# EEZ_DIB_MCU_r1B3.net
KiCad netlist of a schematic drawn in EAGLE
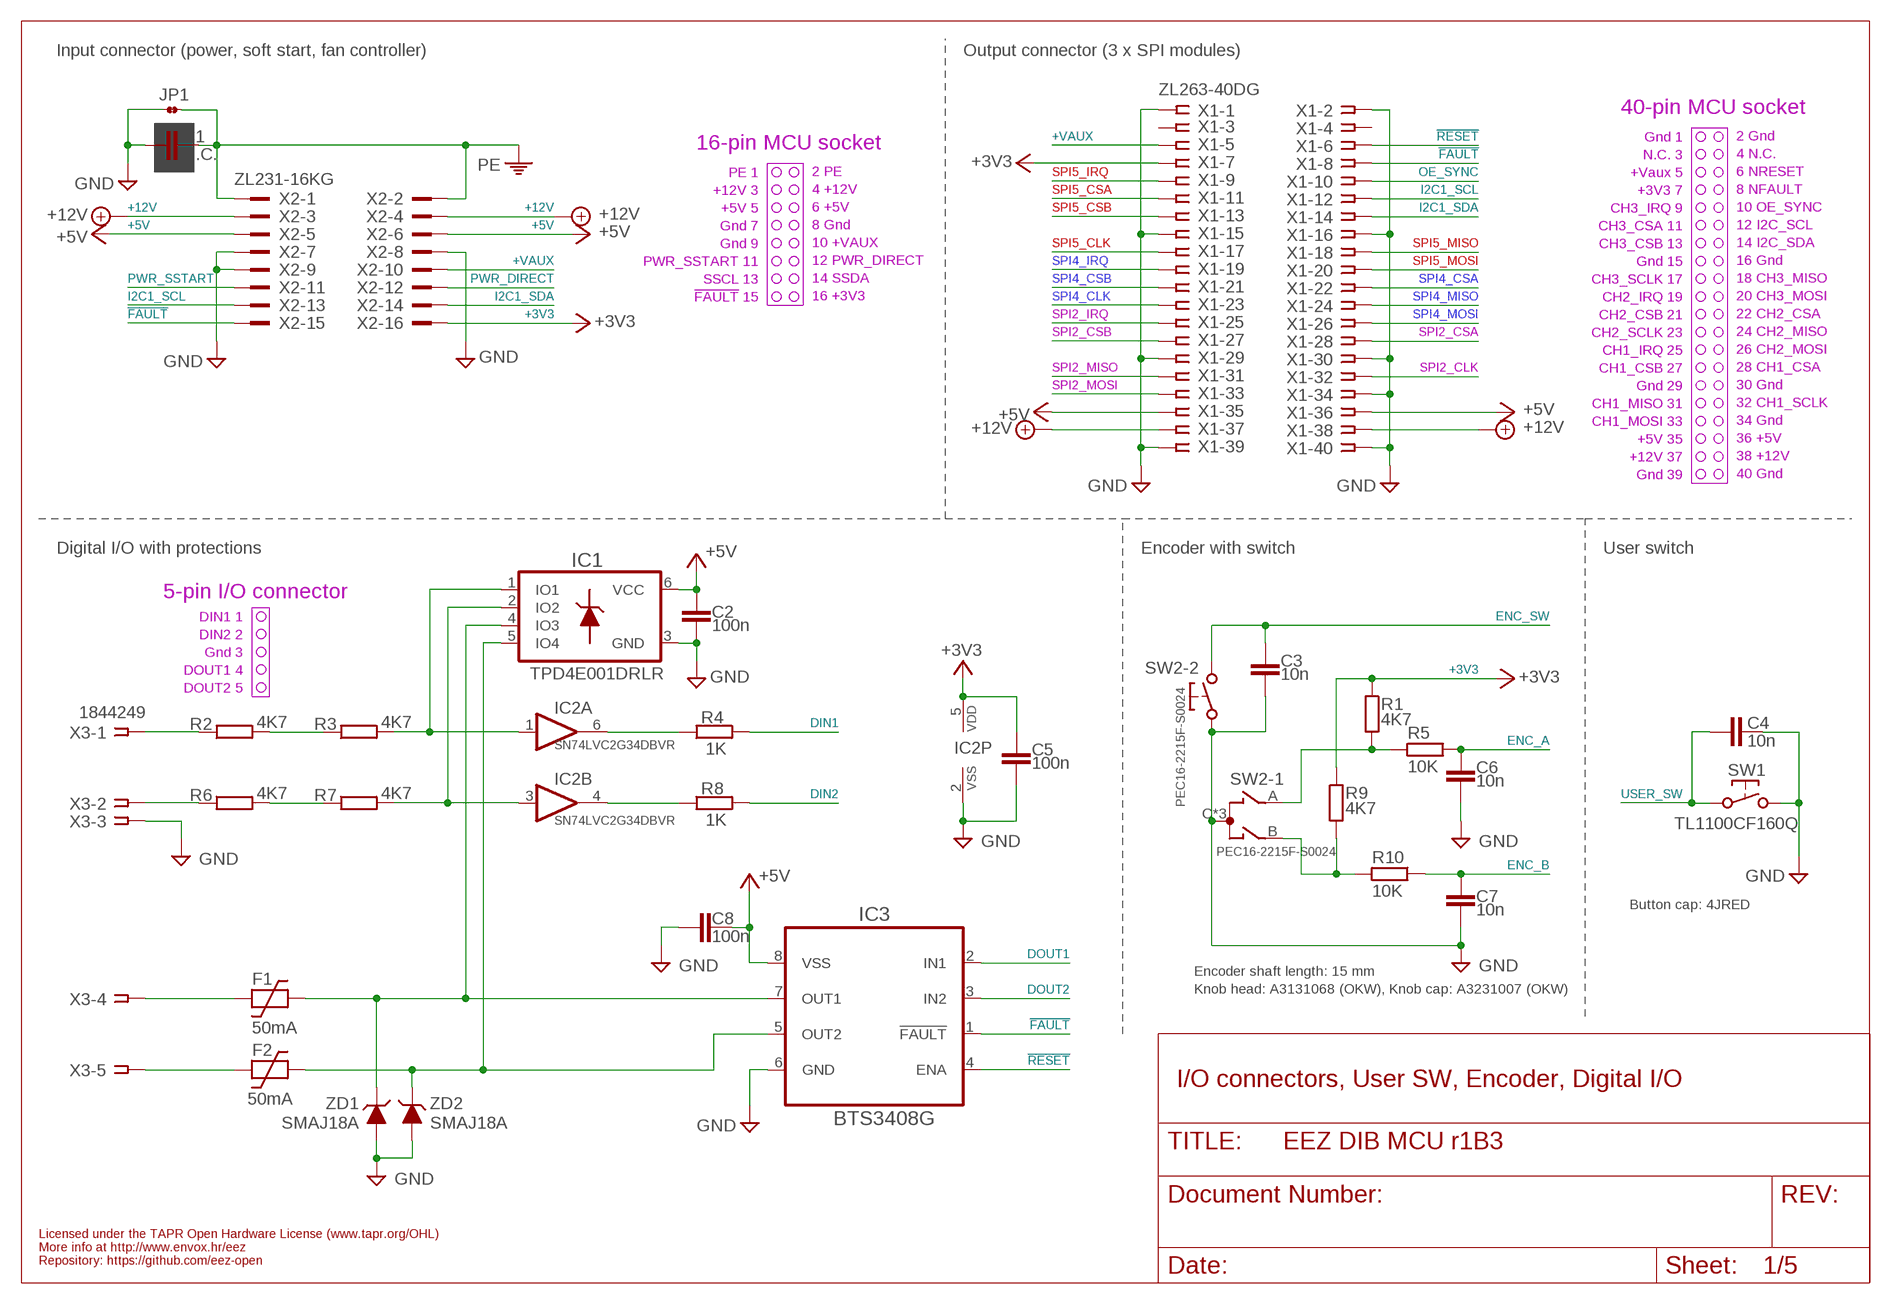
[diagram p0: schematic, sheet 1]
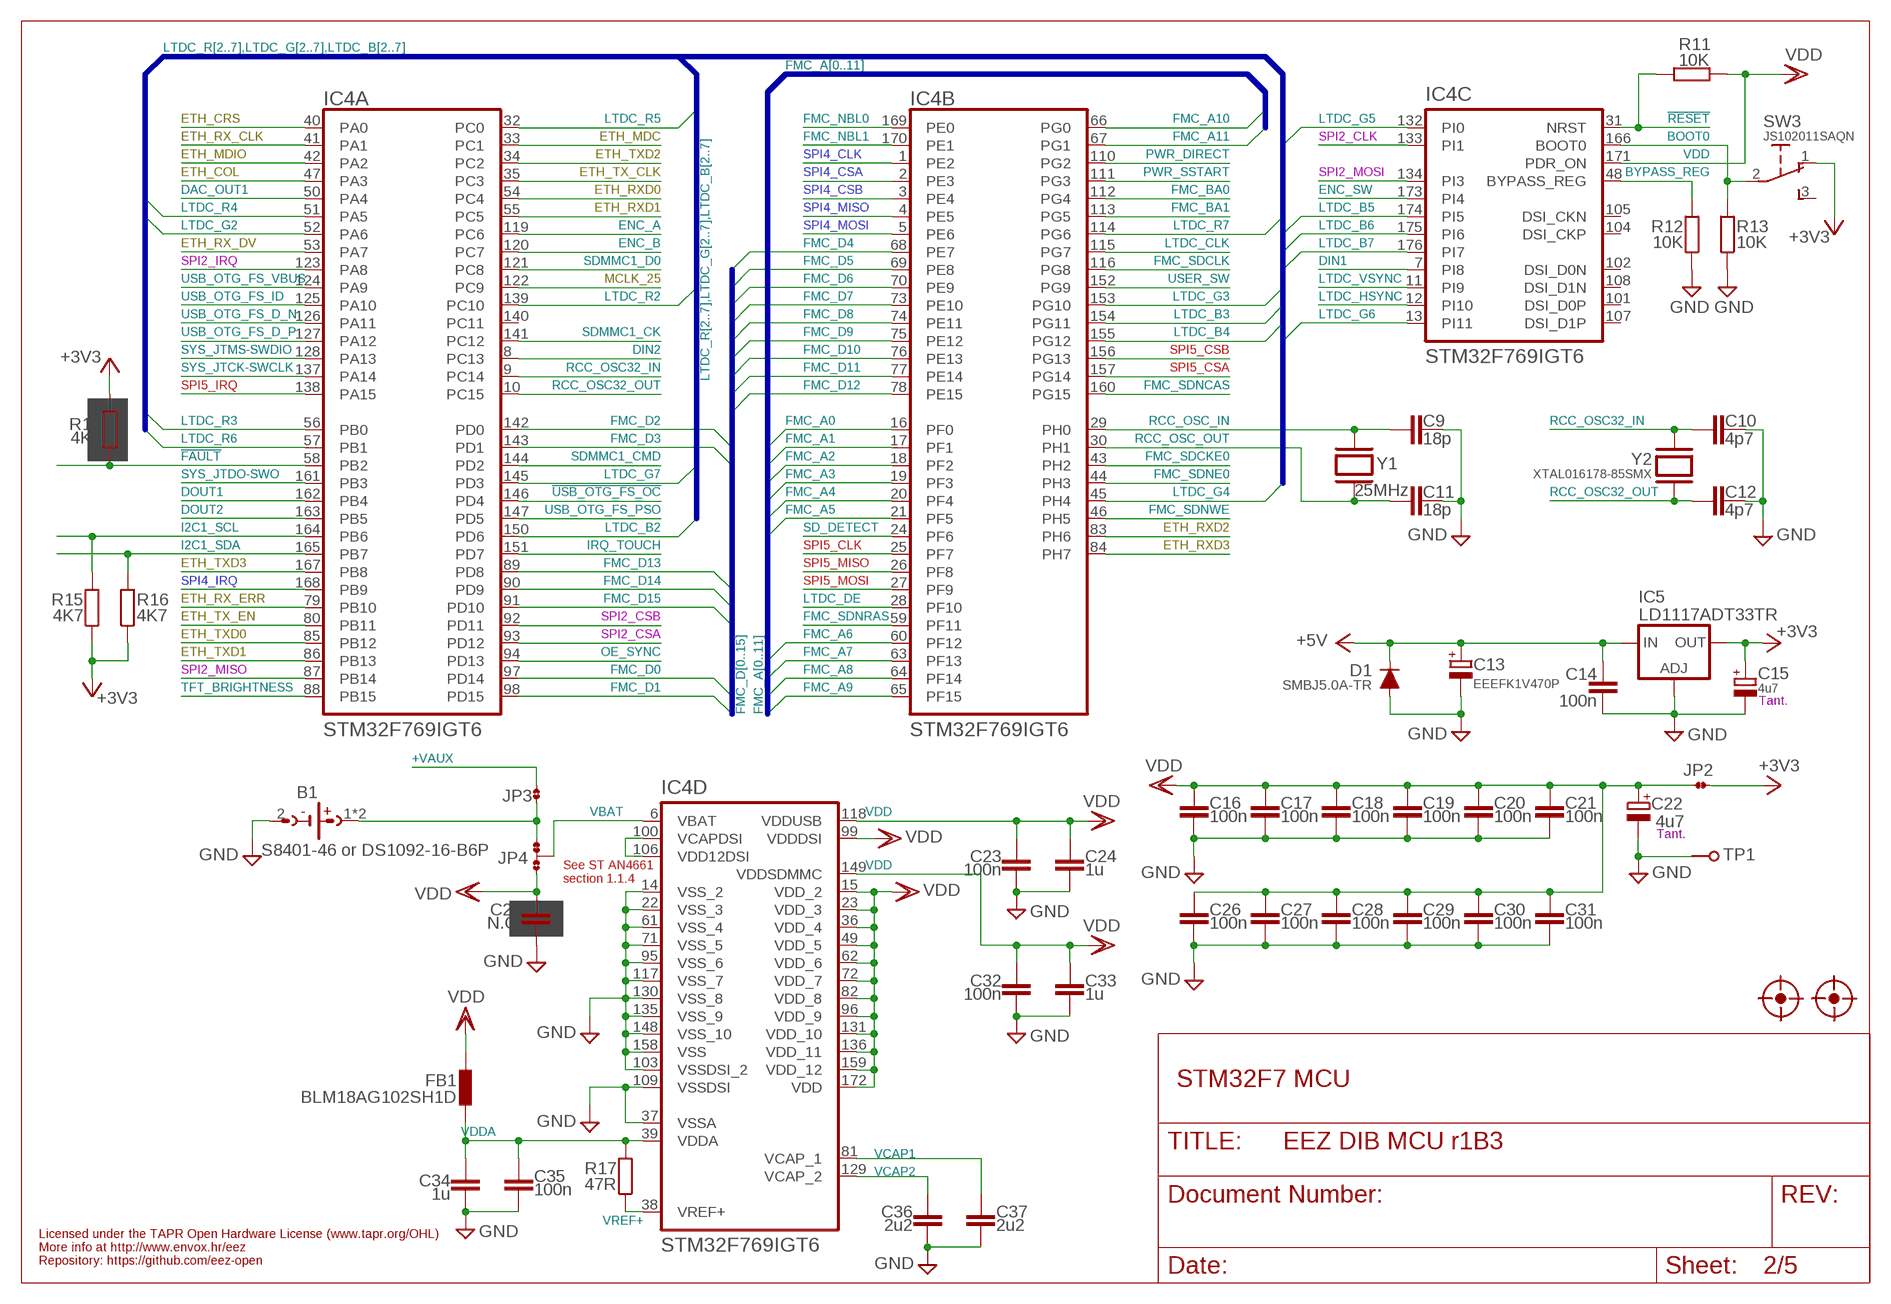
[diagram p1: schematic, sheet 2]
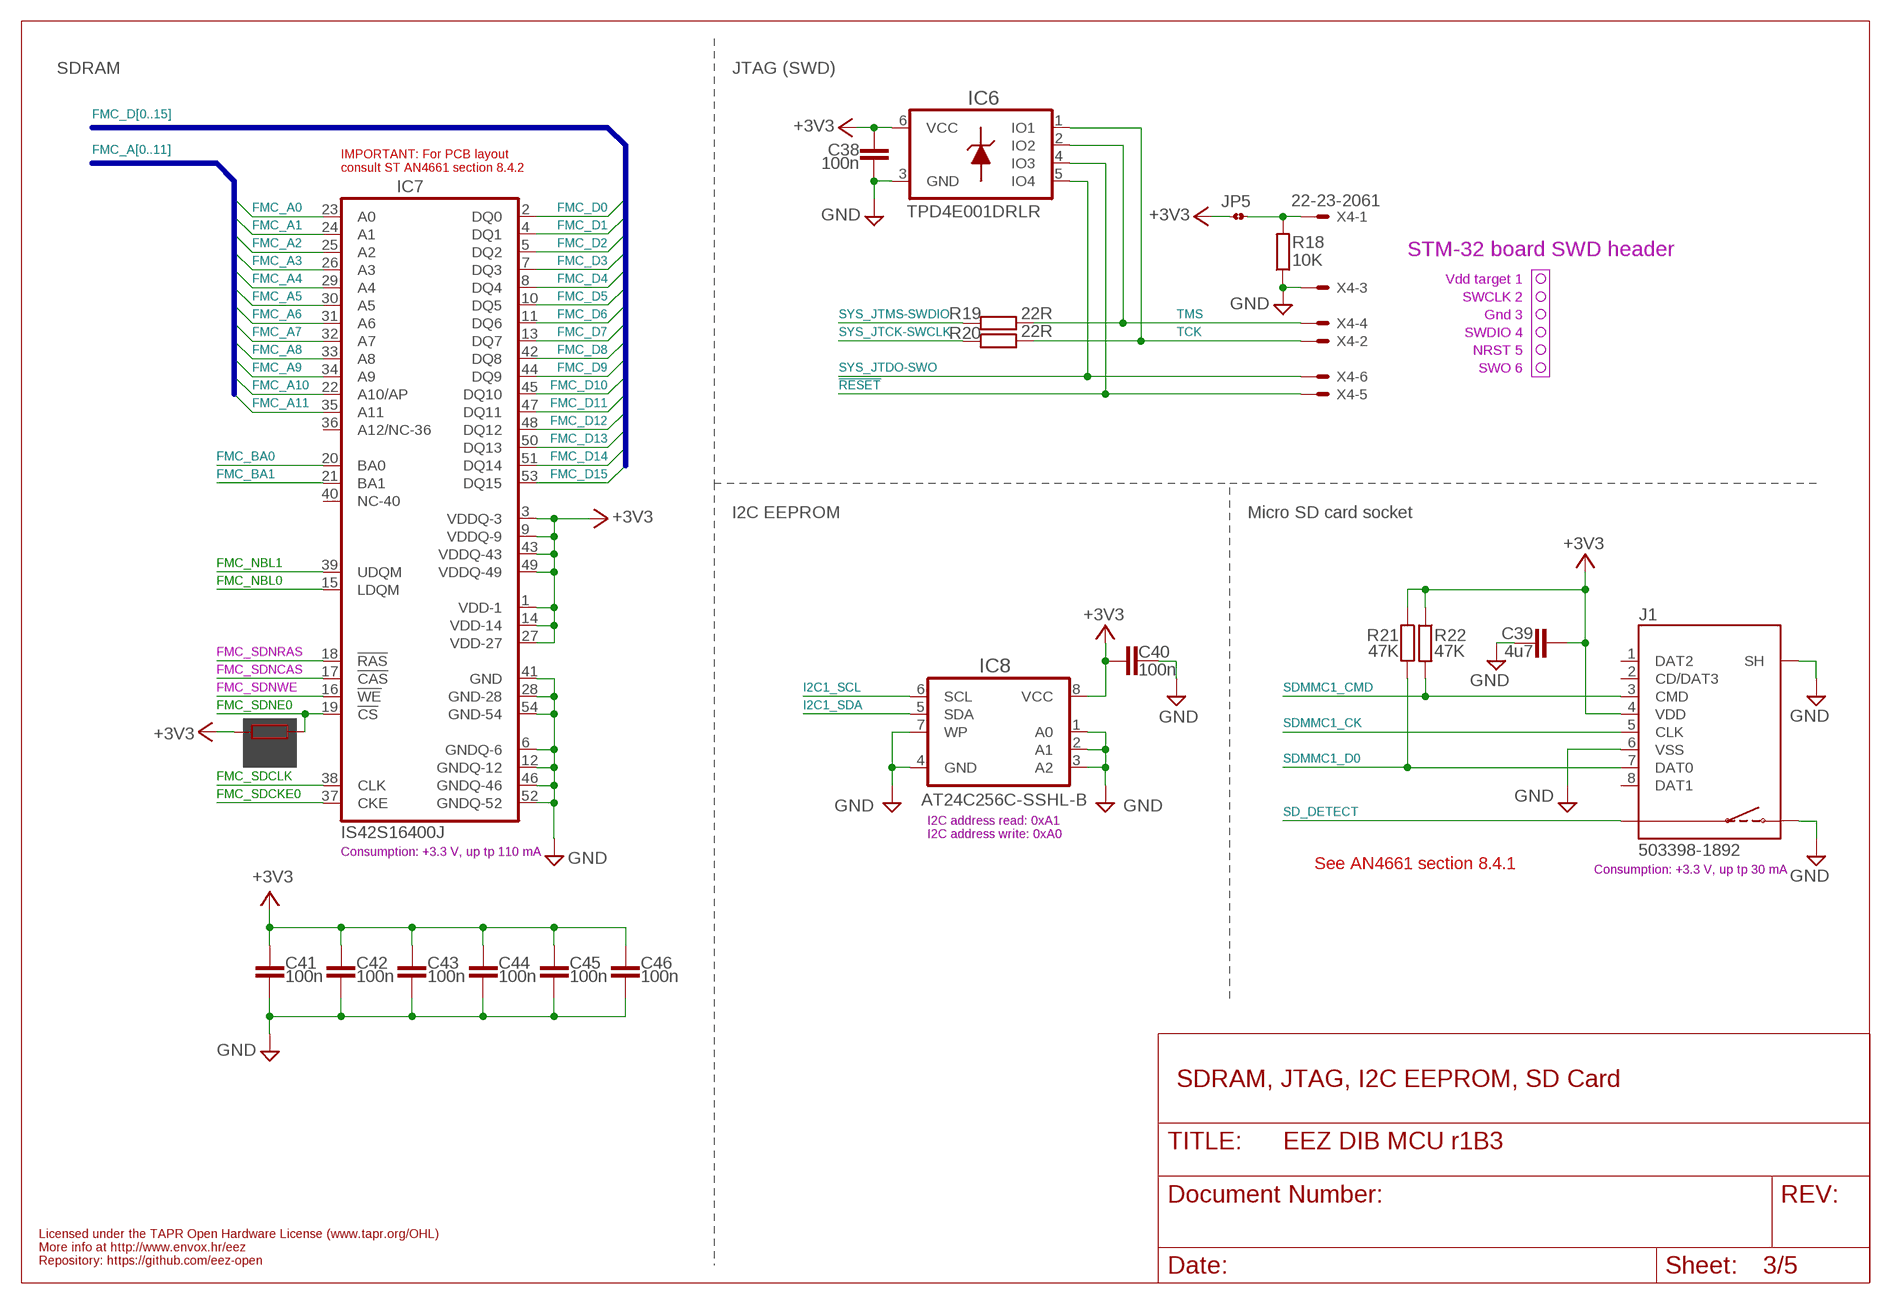
[diagram p2: schematic, sheet 3]
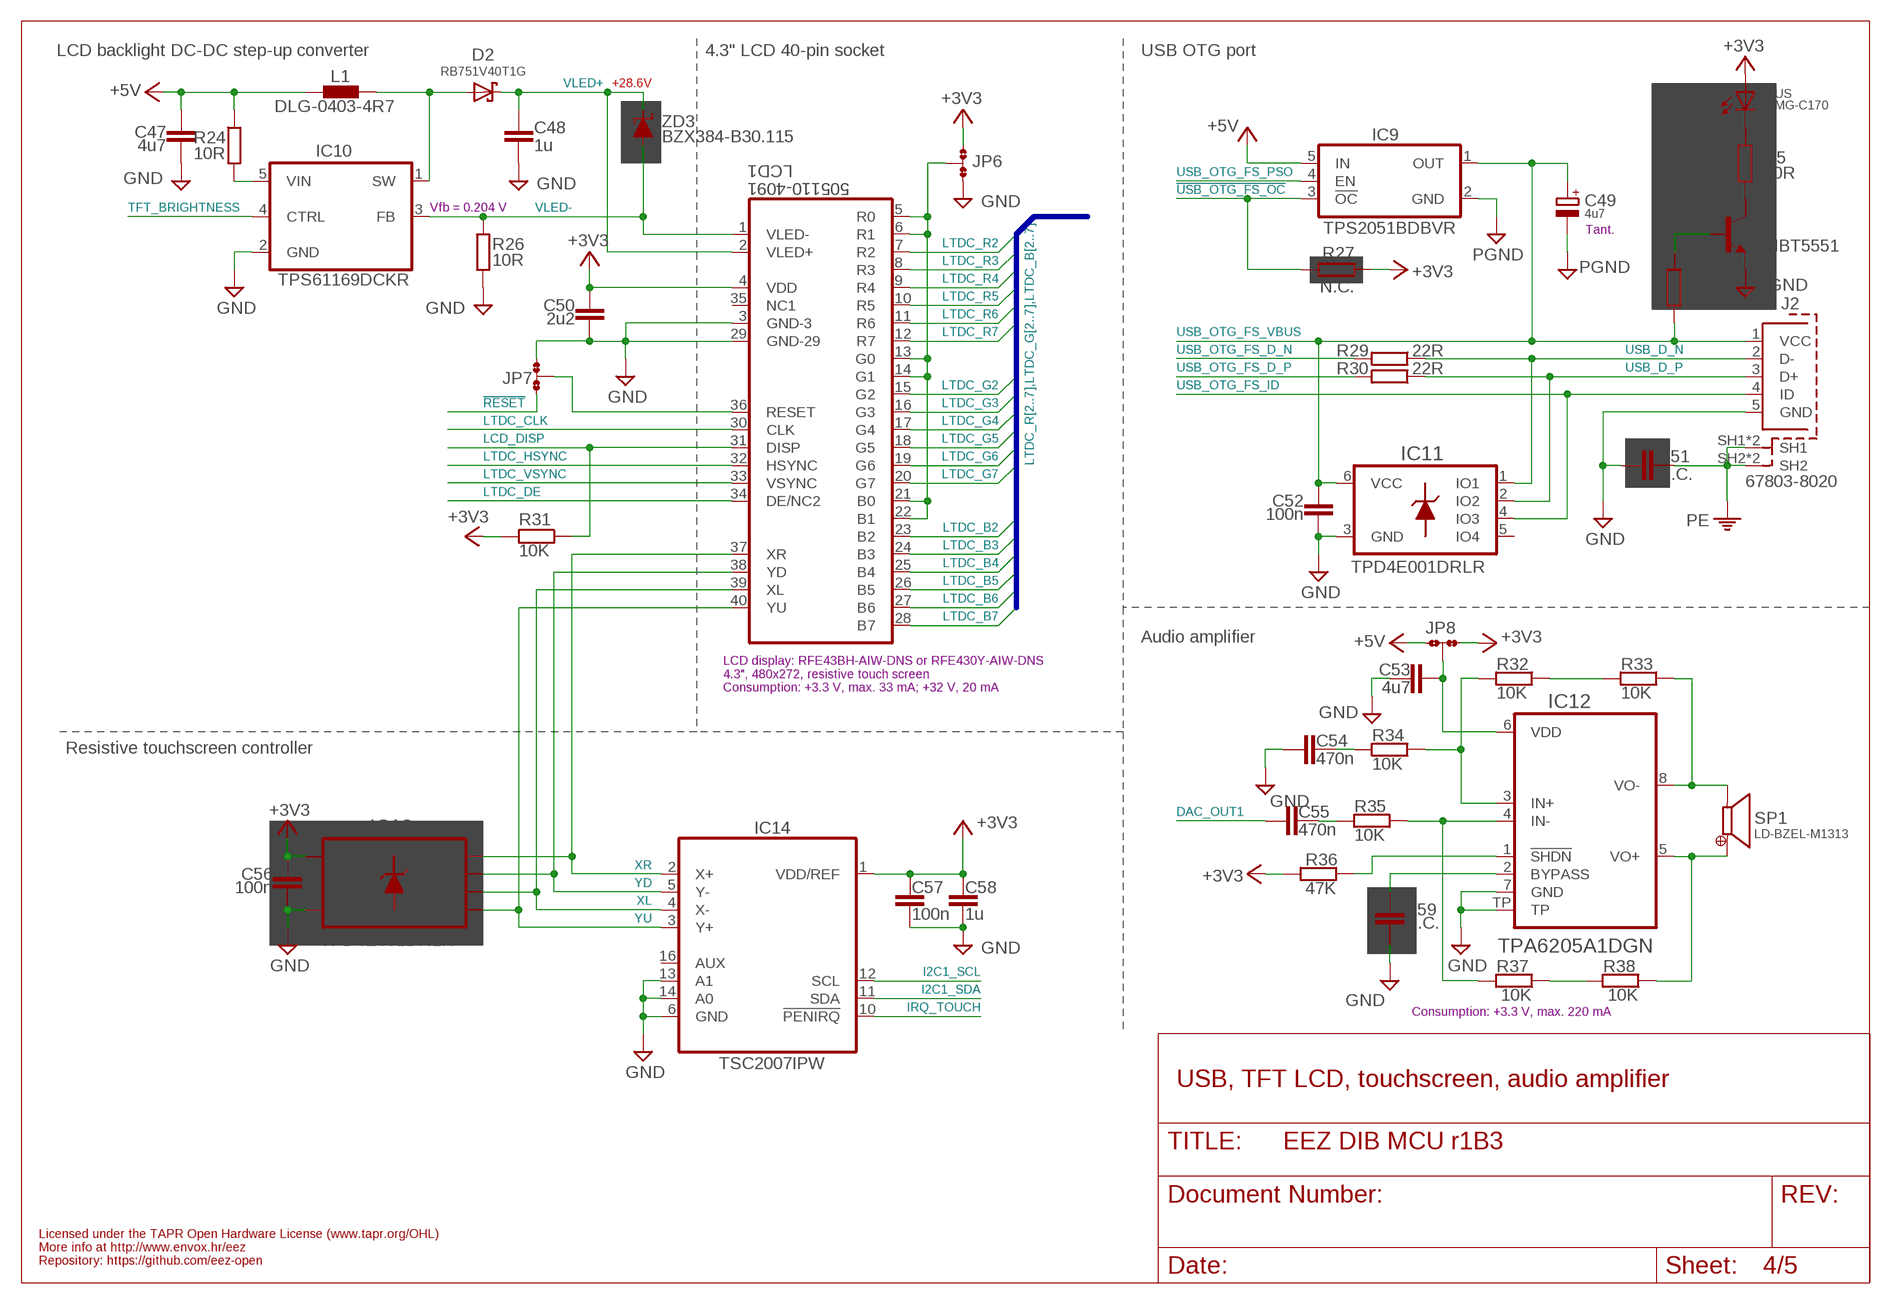
[diagram p3: schematic, sheet 4]
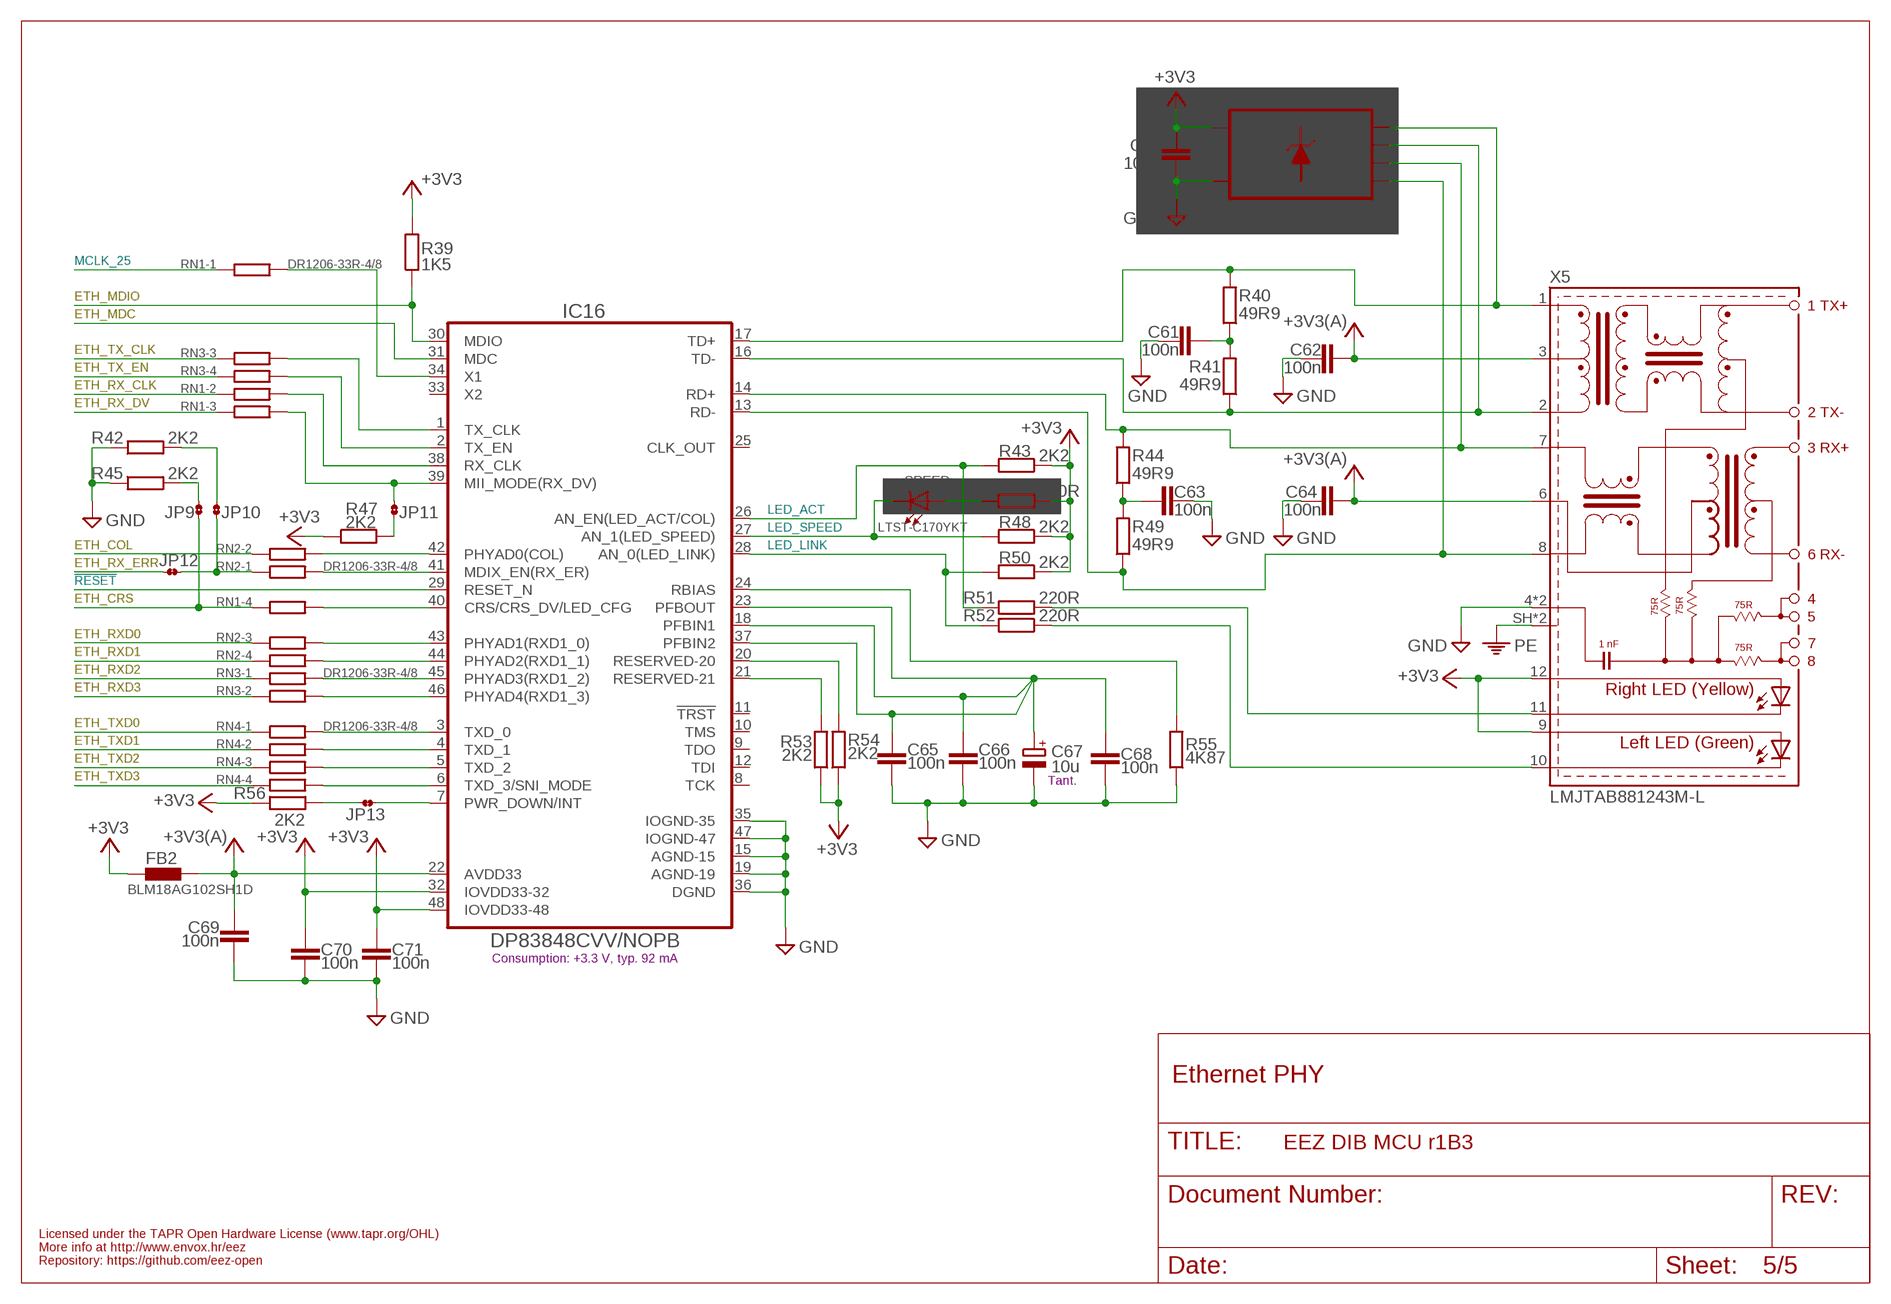
[diagram p4: schematic, sheet 5]

(export (version "E")
  (design (tool "Eeschema 10.0.6"))
  (components
    (comp (ref "C38")
      (value "100n")
      (footprint "eagle-import:C0603")
      (libsource (lib "eagle-import") (part "C-EUC0603"))
    )
    (comp (ref "C39")
      (value "4u7")
      (footprint "eagle-import:C1206")
      (libsource (lib "eagle-import") (part "C-EUC1206"))
    )
    (comp (ref "C40")
      (value "100n")
      (footprint "eagle-import:C0603")
      (libsource (lib "eagle-import") (part "C-EUC0603"))
    )
    (comp (ref "C41")
      (value "100n")
      (footprint "eagle-import:C0603")
      (libsource (lib "eagle-import") (part "C-EUC0603"))
    )
    (comp (ref "C42")
      (value "100n")
      (footprint "eagle-import:C0603")
      (libsource (lib "eagle-import") (part "C-EUC0603"))
    )
    (comp (ref "C43")
      (value "100n")
      (footprint "eagle-import:C0603")
      (libsource (lib "eagle-import") (part "C-EUC0603"))
    )
    (comp (ref "C44")
      (value "100n")
      (footprint "eagle-import:C0603")
      (libsource (lib "eagle-import") (part "C-EUC0603"))
    )
    (comp (ref "C45")
      (value "100n")
      (footprint "eagle-import:C0603")
      (libsource (lib "eagle-import") (part "C-EUC0603"))
    )
    (comp (ref "C46")
      (value "100n")
      (footprint "eagle-import:C0603")
      (libsource (lib "eagle-import") (part "C-EUC0603"))
    )
    (comp (ref "IC6")
      (value "TPD4E001DRLR")
      (footprint "eagle-import:DRL6")
      (libsource (lib "eagle-import") (part "TPD4E001-DRL"))
    )
    (comp (ref "IC7")
      (value "IS42S16400J")
      (footprint "eagle-import:TSOPII-54")
      (libsource (lib "eagle-import") (part "IS42S16400"))
    )
    (comp (ref "IC8")
      (value "AT24C256C-SSHL-B")
      (footprint "eagle-import:SOIC127P600X173-8N")
      (libsource (lib "eagle-import") (part "AT24CXXSOIC8"))
    )
    (comp (ref "J1")
      (value "503398-1892")
      (footprint "eagle-import:5033981892")
      (libsource (lib "eagle-import") (part "5033981892"))
    )
    (comp (ref "JP5")
      (value "JP2-CUT")
      (footprint "eagle-import:JP2-CUT")
      (libsource (lib "eagle-import") (part "JP2-CUT"))
    )
    (comp (ref "R18")
      (value "10K")
      (footprint "eagle-import:R0805")
      (libsource (lib "eagle-import") (part "R-EU_R0805"))
    )
    (comp (ref "R19")
      (value "22R")
      (footprint "eagle-import:R0805")
      (libsource (lib "eagle-import") (part "R-EU_R0805"))
    )
    (comp (ref "R20")
      (value "22R")
      (footprint "eagle-import:R0805")
      (libsource (lib "eagle-import") (part "R-EU_R0805"))
    )
    (comp (ref "R21")
      (value "47K")
      (footprint "eagle-import:R0805")
      (libsource (lib "eagle-import") (part "R-EU_R0805"))
    )
    (comp (ref "R22")
      (value "47K")
      (footprint "eagle-import:R0805")
      (libsource (lib "eagle-import") (part "R-EU_R0805"))
    )
    (comp (ref "R23")
      (value "N.C.")
      (footprint "eagle-import:R0805")
      (libsource (lib "eagle-import") (part "R-EU_R0805"))
    )
    (comp (ref "X4")
      (value "22-23-2061")
      (footprint "eagle-import:22-23-2061")
      (fields (field (name "MF") "MOLEX"))
      (libsource (lib "eagle-import") (part "22-23-2061"))
    )
    (comp (ref "C1")
      (value "N.C.")
      (footprint "eagle-import:C1210")
      (libsource (lib "eagle-import") (part "C-EUC1210"))
    )
    (comp (ref "C2")
      (value "100n")
      (footprint "eagle-import:C0603")
      (libsource (lib "eagle-import") (part "C-EUC0603"))
    )
    (comp (ref "C3")
      (value "10n")
      (footprint "eagle-import:C0805")
      (libsource (lib "eagle-import") (part "C-EUC0805"))
    )
    (comp (ref "C4")
      (value "10n")
      (footprint "eagle-import:C0805")
      (libsource (lib "eagle-import") (part "C-EUC0805"))
    )
    (comp (ref "C5")
      (value "100n")
      (footprint "eagle-import:C0603")
      (libsource (lib "eagle-import") (part "C-EUC0603"))
    )
    (comp (ref "C6")
      (value "10n")
      (footprint "eagle-import:C0805")
      (libsource (lib "eagle-import") (part "C-EUC0805"))
    )
    (comp (ref "C7")
      (value "10n")
      (footprint "eagle-import:C0805")
      (libsource (lib "eagle-import") (part "C-EUC0805"))
    )
    (comp (ref "C8")
      (value "100n")
      (footprint "eagle-import:C0603")
      (libsource (lib "eagle-import") (part "C-EUC0603"))
    )
    (comp (ref "F1")
      (value "50mA")
      (footprint "eagle-import:F1210")
      (libsource (lib "eagle-import") (part "FUSE_RESETTABLE21210"))
    )
    (comp (ref "F2")
      (value "50mA")
      (footprint "eagle-import:F1210")
      (libsource (lib "eagle-import") (part "FUSE_RESETTABLE21210"))
    )
    (comp (ref "IC1")
      (value "TPD4E001DRLR")
      (footprint "eagle-import:DRL6")
      (libsource (lib "eagle-import") (part "TPD4E001-DRL"))
    )
    (comp (ref "IC2")
      (value "SN74LVC2G34DBVR")
      (footprint "eagle-import:DBV6")
      (libsource (lib "eagle-import") (part "SN74LVC2G34DBVR"))
    )
    (comp (ref "IC3")
      (value "BTS3408G")
      (footprint "eagle-import:SOIC127P600X173-8N")
      (libsource (lib "eagle-import") (part "BTS3408G"))
    )
    (comp (ref "JP1")
      (value "JP2-NOCUT")
      (footprint "eagle-import:JP2-NOCUT")
      (libsource (lib "eagle-import") (part "JP2-NOCUT"))
    )
    (comp (ref "R1")
      (value "4K7")
      (footprint "eagle-import:R0805")
      (libsource (lib "eagle-import") (part "R-EU_R0805"))
    )
    (comp (ref "R2")
      (value "4K7")
      (footprint "eagle-import:R0805")
      (libsource (lib "eagle-import") (part "R-EU_R0805"))
    )
    (comp (ref "R3")
      (value "4K7")
      (footprint "eagle-import:R0805")
      (libsource (lib "eagle-import") (part "R-EU_R0805"))
    )
    (comp (ref "R4")
      (value "1K")
      (footprint "eagle-import:R0805")
      (libsource (lib "eagle-import") (part "R-EU_R0805"))
    )
    (comp (ref "R5")
      (value "10K")
      (footprint "eagle-import:R0805")
      (libsource (lib "eagle-import") (part "R-EU_R0805"))
    )
    (comp (ref "R6")
      (value "4K7")
      (footprint "eagle-import:R0805")
      (libsource (lib "eagle-import") (part "R-EU_R0805"))
    )
    (comp (ref "R7")
      (value "4K7")
      (footprint "eagle-import:R0805")
      (libsource (lib "eagle-import") (part "R-EU_R0805"))
    )
    (comp (ref "R8")
      (value "1K")
      (footprint "eagle-import:R0805")
      (libsource (lib "eagle-import") (part "R-EU_R0805"))
    )
    (comp (ref "R9")
      (value "4K7")
      (footprint "eagle-import:R0805")
      (libsource (lib "eagle-import") (part "R-EU_R0805"))
    )
    (comp (ref "R10")
      (value "10K")
      (footprint "eagle-import:R0805")
      (libsource (lib "eagle-import") (part "R-EU_R0805"))
    )
    (comp (ref "SW1")
      (value "TL1100CF160Q")
      (footprint "eagle-import:TL1100C")
      (libsource (lib "eagle-import") (part "TL1100C"))
    )
    (comp (ref "SW2")
      (value "PEC16-2215F-S0024")
      (footprint "eagle-import:PEC16-2215F")
      (libsource (lib "eagle-import") (part "ENCODER_SW-PEC16"))
    )
    (comp (ref "X1")
      (value "ZL263-40DG")
      (footprint "eagle-import:ZL263-40DG")
      (libsource (lib "eagle-import") (part "ZL263-40DG"))
    )
    (comp (ref "X2")
      (value "ZL231-16KG")
      (footprint "eagle-import:ML16L")
      (libsource (lib "eagle-import") (part "IDC-16PIN-ANGLED"))
    )
    (comp (ref "X3")
      (value "1844249")
      (footprint "eagle-import:MC1,5_5-G-3,5")
      (libsource (lib "eagle-import") (part "MC1,5/5-G-3,5"))
    )
    (comp (ref "ZD1")
      (value "SMAJ18A")
      (footprint "eagle-import:DO214AC")
      (libsource (lib "eagle-import") (part "PSMAXX"))
    )
    (comp (ref "ZD2")
      (value "SMAJ18A")
      (footprint "eagle-import:DO214AC")
      (libsource (lib "eagle-import") (part "PSMAXX"))
    )
    (comp (ref "C47")
      (value "4u7")
      (footprint "eagle-import:C1206")
      (libsource (lib "eagle-import") (part "C-EUC1206"))
    )
    (comp (ref "C48")
      (value "1u")
      (footprint "eagle-import:C0805")
      (libsource (lib "eagle-import") (part "C-EUC0805"))
    )
    (comp (ref "C49")
      (value "4u7")
      (footprint "eagle-import:EC1206")
      (libsource (lib "eagle-import") (part "ECAP1206"))
    )
    (comp (ref "C50")
      (value "2u2")
      (footprint "eagle-import:C0805")
      (libsource (lib "eagle-import") (part "C-EUC0805"))
    )
    (comp (ref "C51")
      (value "N.C.")
      (footprint "eagle-import:C1210")
      (libsource (lib "eagle-import") (part "C-EUC1210"))
    )
    (comp (ref "C52")
      (value "100n")
      (footprint "eagle-import:C0603")
      (libsource (lib "eagle-import") (part "C-EUC0603"))
    )
    (comp (ref "C53")
      (value "4u7")
      (footprint "eagle-import:C1206")
      (libsource (lib "eagle-import") (part "C-EUC1206"))
    )
    (comp (ref "C54")
      (value "470n")
      (footprint "eagle-import:C0805")
      (libsource (lib "eagle-import") (part "C-EUC0805"))
    )
    (comp (ref "C55")
      (value "470n")
      (footprint "eagle-import:C0805")
      (libsource (lib "eagle-import") (part "C-EUC0805"))
    )
    (comp (ref "C56")
      (value "100n")
      (footprint "eagle-import:C0603")
      (libsource (lib "eagle-import") (part "C-EUC0603"))
    )
    (comp (ref "C57")
      (value "100n")
      (footprint "eagle-import:C0603")
      (libsource (lib "eagle-import") (part "C-EUC0603"))
    )
    (comp (ref "C58")
      (value "1u")
      (footprint "eagle-import:C0805")
      (libsource (lib "eagle-import") (part "C-EUC0805"))
    )
    (comp (ref "C59")
      (value "N.C.")
      (footprint "eagle-import:C0805")
      (libsource (lib "eagle-import") (part "C-EUC0805"))
    )
    (comp (ref "D2")
      (value "RB751V40T1G")
      (footprint "eagle-import:SOD323-R")
      (libsource (lib "eagle-import") (part "SCHOTTKYSOD-323R"))
    )
    (comp (ref "IC9")
      (value "TPS2051BDBVR")
      (footprint "eagle-import:DBV5")
      (libsource (lib "eagle-import") (part "TPS2051B"))
    )
    (comp (ref "IC10")
      (value "TPS61169DCKR")
      (footprint "eagle-import:DCK5")
      (fields (field (name "MANUFACTURER") "Texas Instruments"))
      (libsource (lib "eagle-import") (part "TPS61169DCKR"))
    )
    (comp (ref "IC11")
      (value "TPD4E001DRLR")
      (footprint "eagle-import:DRL6")
      (libsource (lib "eagle-import") (part "TPD4E001-DRL"))
    )
    (comp (ref "IC12")
      (value "TPA6205A1DGN")
      (footprint "eagle-import:SOP65P490X110-9N")
      (libsource (lib "eagle-import") (part "TPA6205"))
    )
    (comp (ref "IC13")
      (value "TPD4E001DRLR")
      (footprint "eagle-import:DRL6")
      (libsource (lib "eagle-import") (part "TPD4E001-DRL"))
    )
    (comp (ref "IC14")
      (value "TSC2007IPW")
      (footprint "eagle-import:PW(R-PDSO-G16)")
      (libsource (lib "eagle-import") (part "TSC2007IPW"))
    )
    (comp (ref "J2")
      (value "67803-8020")
      (footprint "eagle-import:678038020")
      (libsource (lib "eagle-import") (part "678038020"))
    )
    (comp (ref "JP6")
      (value "JP3-CUT")
      (footprint "eagle-import:JP3-CUT")
      (libsource (lib "eagle-import") (part "JP3-CUT"))
    )
    (comp (ref "JP7")
      (value "JP3-CUT")
      (footprint "eagle-import:JP3-CUT")
      (libsource (lib "eagle-import") (part "JP3-CUT"))
    )
    (comp (ref "JP8")
      (value "JP3-CUT")
      (footprint "eagle-import:JP3-CUT")
      (libsource (lib "eagle-import") (part "JP3-CUT"))
    )
    (comp (ref "L1")
      (value "DLG-0403-4R7")
      (footprint "eagle-import:DE0403")
      (libsource (lib "eagle-import") (part "DE0403"))
    )
    (comp (ref "LCD1")
      (value "505110-4091")
      (footprint "eagle-import:FPC_40")
      (libsource (lib "eagle-import") (part "RFE430Y-AIW-DNS"))
    )
    (comp (ref "Q1")
      (value "MMBT5551")
      (footprint "eagle-import:SOT23-BEC")
      (libsource (lib "eagle-import") (part "-NPN-SOT23-BECMMBT5551LT1"))
    )
    (comp (ref "R24")
      (value "10R")
      (footprint "eagle-import:R0805")
      (libsource (lib "eagle-import") (part "R-EU_R0805"))
    )
    (comp (ref "R25")
      (value "330R")
      (footprint "eagle-import:R0805")
      (libsource (lib "eagle-import") (part "R-EU_R0805"))
    )
    (comp (ref "R26")
      (value "10R")
      (footprint "eagle-import:R0805")
      (libsource (lib "eagle-import") (part "R-EU_R0805"))
    )
    (comp (ref "R27")
      (value "N.C.")
      (footprint "eagle-import:R0805")
      (libsource (lib "eagle-import") (part "R-EU_R0805"))
    )
    (comp (ref "R28")
      (value "47K")
      (footprint "eagle-import:R0805")
      (libsource (lib "eagle-import") (part "R-EU_R0805"))
    )
    (comp (ref "R29")
      (value "22R")
      (footprint "eagle-import:R0805")
      (libsource (lib "eagle-import") (part "R-EU_R0805"))
    )
    (comp (ref "R30")
      (value "22R")
      (footprint "eagle-import:R0805")
      (libsource (lib "eagle-import") (part "R-EU_R0805"))
    )
    (comp (ref "R31")
      (value "10K")
      (footprint "eagle-import:R0805")
      (libsource (lib "eagle-import") (part "R-EU_R0805"))
    )
    (comp (ref "R32")
      (value "10K")
      (footprint "eagle-import:R0805")
      (libsource (lib "eagle-import") (part "R-EU_R0805"))
    )
    (comp (ref "R33")
      (value "10K")
      (footprint "eagle-import:R0805")
      (libsource (lib "eagle-import") (part "R-EU_R0805"))
    )
    (comp (ref "R34")
      (value "10K")
      (footprint "eagle-import:R0805")
      (libsource (lib "eagle-import") (part "R-EU_R0805"))
    )
    (comp (ref "R35")
      (value "10K")
      (footprint "eagle-import:R0805")
      (libsource (lib "eagle-import") (part "R-EU_R0805"))
    )
    (comp (ref "R36")
      (value "47K")
      (footprint "eagle-import:R0805")
      (libsource (lib "eagle-import") (part "R-EU_R0805"))
    )
    (comp (ref "R37")
      (value "10K")
      (footprint "eagle-import:R0805")
      (libsource (lib "eagle-import") (part "R-EU_R0805"))
    )
    (comp (ref "R38")
      (value "10K")
      (footprint "eagle-import:R0805")
      (libsource (lib "eagle-import") (part "R-EU_R0805"))
    )
    (comp (ref "SP1")
      (value "LD-BZEL-M1313")
      (footprint "eagle-import:LD-BZEL-M1313")
      (libsource (lib "eagle-import") (part "LD-BZEL-M1313"))
    )
    (comp (ref "VBUS")
      (value "HSMG-C170")
      (footprint "eagle-import:LED_0805")
      (libsource (lib "eagle-import") (part "LED0805"))
    )
    (comp (ref "ZD3")
      (value "BZX384-B30.115")
      (footprint "eagle-import:SOD323-W")
      (libsource (lib "eagle-import") (part "ZENER-DIODESOD323"))
    )
    (comp (ref "B1")
      (value "S8401-46 or DS1092-16-B6P")
      (footprint "eagle-import:S8401-46")
      (libsource (lib "eagle-import") (part "CELL_BATTERYVERT"))
    )
    (comp (ref "C9")
      (value "18p")
      (footprint "eagle-import:C0603")
      (libsource (lib "eagle-import") (part "C-EUC0603"))
    )
    (comp (ref "C10")
      (value "4p7")
      (footprint "eagle-import:C0603")
      (libsource (lib "eagle-import") (part "C-EUC0603"))
    )
    (comp (ref "C11")
      (value "18p")
      (footprint "eagle-import:C0603")
      (libsource (lib "eagle-import") (part "C-EUC0603"))
    )
    (comp (ref "C12")
      (value "4p7")
      (footprint "eagle-import:C0603")
      (libsource (lib "eagle-import") (part "C-EUC0603"))
    )
    (comp (ref "C13")
      (value "EEEFK1V470P")
      (footprint "eagle-import:CAPAE660X610N")
      (libsource (lib "eagle-import") (part "ECAPPANASONIC_H"))
    )
    (comp (ref "C14")
      (value "100n")
      (footprint "eagle-import:C0603")
      (libsource (lib "eagle-import") (part "C-EUC0603"))
    )
    (comp (ref "C15")
      (value "4u7")
      (footprint "eagle-import:EC1206")
      (libsource (lib "eagle-import") (part "ECAP1206"))
    )
    (comp (ref "C16")
      (value "100n")
      (footprint "eagle-import:C0603")
      (libsource (lib "eagle-import") (part "C-EUC0603"))
    )
    (comp (ref "C17")
      (value "100n")
      (footprint "eagle-import:C0603")
      (libsource (lib "eagle-import") (part "C-EUC0603"))
    )
    (comp (ref "C18")
      (value "100n")
      (footprint "eagle-import:C0603")
      (libsource (lib "eagle-import") (part "C-EUC0603"))
    )
    (comp (ref "C19")
      (value "100n")
      (footprint "eagle-import:C0603")
      (libsource (lib "eagle-import") (part "C-EUC0603"))
    )
    (comp (ref "C20")
      (value "100n")
      (footprint "eagle-import:C0603")
      (libsource (lib "eagle-import") (part "C-EUC0603"))
    )
    (comp (ref "C21")
      (value "100n")
      (footprint "eagle-import:C0603")
      (libsource (lib "eagle-import") (part "C-EUC0603"))
    )
    (comp (ref "C22")
      (value "4u7")
      (footprint "eagle-import:EC1206")
      (libsource (lib "eagle-import") (part "ECAP1206"))
    )
    (comp (ref "C23")
      (value "100n")
      (footprint "eagle-import:C0603")
      (libsource (lib "eagle-import") (part "C-EUC0603"))
    )
    (comp (ref "C24")
      (value "1u")
      (footprint "eagle-import:C0805")
      (libsource (lib "eagle-import") (part "C-EUC0805"))
    )
    (comp (ref "C25")
      (value "N.C.")
      (footprint "eagle-import:C0603")
      (libsource (lib "eagle-import") (part "C-EUC0603"))
    )
    (comp (ref "C26")
      (value "100n")
      (footprint "eagle-import:C0603")
      (libsource (lib "eagle-import") (part "C-EUC0603"))
    )
    (comp (ref "C27")
      (value "100n")
      (footprint "eagle-import:C0603")
      (libsource (lib "eagle-import") (part "C-EUC0603"))
    )
    (comp (ref "C28")
      (value "100n")
      (footprint "eagle-import:C0603")
      (libsource (lib "eagle-import") (part "C-EUC0603"))
    )
    (comp (ref "C29")
      (value "100n")
      (footprint "eagle-import:C0603")
      (libsource (lib "eagle-import") (part "C-EUC0603"))
    )
    (comp (ref "C30")
      (value "100n")
      (footprint "eagle-import:C0603")
      (libsource (lib "eagle-import") (part "C-EUC0603"))
    )
    (comp (ref "C31")
      (value "100n")
      (footprint "eagle-import:C0603")
      (libsource (lib "eagle-import") (part "C-EUC0603"))
    )
    (comp (ref "C32")
      (value "100n")
      (footprint "eagle-import:C0603")
      (libsource (lib "eagle-import") (part "C-EUC0603"))
    )
    (comp (ref "C33")
      (value "1u")
      (footprint "eagle-import:C0805")
      (libsource (lib "eagle-import") (part "C-EUC0805"))
    )
    (comp (ref "C34")
      (value "1u")
      (footprint "eagle-import:C0805")
      (libsource (lib "eagle-import") (part "C-EUC0805"))
    )
    (comp (ref "C35")
      (value "100n")
      (footprint "eagle-import:C0603")
      (libsource (lib "eagle-import") (part "C-EUC0603"))
    )
    (comp (ref "C36")
      (value "2u2")
      (footprint "eagle-import:C0805")
      (libsource (lib "eagle-import") (part "C-EUC0805"))
    )
    (comp (ref "C37")
      (value "2u2")
      (footprint "eagle-import:C0805")
      (libsource (lib "eagle-import") (part "C-EUC0805"))
    )
    (comp (ref "D1")
      (value "SMBJ5.0A-TR")
      (footprint "eagle-import:DO214AA")
      (libsource (lib "eagle-import") (part "DIODEDO214AA"))
    )
    (comp (ref "FB1")
      (value "BLM18AG102SH1D")
      (footprint "eagle-import:BEAD0603")
      (libsource (lib "eagle-import") (part "FERRITE_BEAD0603"))
    )
    (comp (ref "FM1")
      (value "FIDUCIAL")
      (footprint "eagle-import:FIDUCIAL")
      (libsource (lib "eagle-import") (part "FIDUCIAL"))
    )
    (comp (ref "FM2")
      (value "FIDUCIAL")
      (footprint "eagle-import:FIDUCIAL")
      (libsource (lib "eagle-import") (part "FIDUCIAL"))
    )
    (comp (ref "IC4")
      (value "STM32F769IGT6")
      (footprint "eagle-import:LQFP-176_24X24MM")
      (fields
        (field (name "MANUFACTURER_PART_NUMBER") "stm32f769ixt")
        (field (name "COPYRIGHT") "Copyright C 2016 Accelerated Designs. All rights reserved")
      )
      (libsource (lib "eagle-import") (part "STM32F769IXT"))
    )
    (comp (ref "IC5")
      (value "LD1117ADT33TR")
      (footprint "eagle-import:DPACK")
      (libsource (lib "eagle-import") (part "LD117A?DT33TR"))
    )
    (comp (ref "JP2")
      (value "JP2-NOCUT")
      (footprint "eagle-import:JP2-NOCUT")
      (libsource (lib "eagle-import") (part "JP2-NOCUT"))
    )
    (comp (ref "JP3")
      (value "JP2-CUT")
      (footprint "eagle-import:JP2-CUT")
      (libsource (lib "eagle-import") (part "JP2-CUT"))
    )
    (comp (ref "JP4")
      (value "JP3-CUT")
      (footprint "eagle-import:JP3-CUT")
      (libsource (lib "eagle-import") (part "JP3-CUT"))
    )
    (comp (ref "R11")
      (value "10K")
      (footprint "eagle-import:R0805")
      (libsource (lib "eagle-import") (part "R-EU_R0805"))
    )
    (comp (ref "R12")
      (value "10K")
      (footprint "eagle-import:R0805")
      (libsource (lib "eagle-import") (part "R-EU_R0805"))
    )
    (comp (ref "R13")
      (value "10K")
      (footprint "eagle-import:R0805")
      (libsource (lib "eagle-import") (part "R-EU_R0805"))
    )
    (comp (ref "R14")
      (value "4K7")
      (footprint "eagle-import:R0805")
      (libsource (lib "eagle-import") (part "R-EU_R0805"))
    )
    (comp (ref "R15")
      (value "4K7")
      (footprint "eagle-import:R0805")
      (libsource (lib "eagle-import") (part "R-EU_R0805"))
    )
    (comp (ref "R16")
      (value "4K7")
      (footprint "eagle-import:R0805")
      (libsource (lib "eagle-import") (part "R-EU_R0805"))
    )
    (comp (ref "R17")
      (value "47R")
      (footprint "eagle-import:R0805")
      (libsource (lib "eagle-import") (part "R-EU_R0805"))
    )
    (comp (ref "SW3")
      (value "JS102011SAQN")
      (footprint "eagle-import:JS102011SAQN")
      (libsource (lib "eagle-import") (part "JS102011SAQN"))
    )
    (comp (ref "TP1")
      (value "PCB_TEST_TABSHIELD")
      (footprint "eagle-import:PCB_SHIELD_TAB")
      (libsource (lib "eagle-import") (part "PCB_TEST_TABSHIELD"))
    )
    (comp (ref "Y1")
      (value "25MHz")
      (footprint "eagle-import:HC-49_4H")
      (libsource (lib "eagle-import") (part "XTALSMD"))
    )
    (comp (ref "Y2")
      (value "XTAL016178-85SMX")
      (footprint "eagle-import:85SMX")
      (libsource (lib "eagle-import") (part "XTAL85SMX"))
    )
    (comp (ref "C60")
      (value "100n")
      (footprint "eagle-import:C0603")
      (libsource (lib "eagle-import") (part "C-EUC0603"))
    )
    (comp (ref "C61")
      (value "100n")
      (footprint "eagle-import:C0603")
      (libsource (lib "eagle-import") (part "C-EUC0603"))
    )
    (comp (ref "C62")
      (value "100n")
      (footprint "eagle-import:C0603")
      (libsource (lib "eagle-import") (part "C-EUC0603"))
    )
    (comp (ref "C63")
      (value "100n")
      (footprint "eagle-import:C0603")
      (libsource (lib "eagle-import") (part "C-EUC0603"))
    )
    (comp (ref "C64")
      (value "100n")
      (footprint "eagle-import:C0603")
      (libsource (lib "eagle-import") (part "C-EUC0603"))
    )
    (comp (ref "C65")
      (value "100n")
      (footprint "eagle-import:C0603")
      (libsource (lib "eagle-import") (part "C-EUC0603"))
    )
    (comp (ref "C66")
      (value "100n")
      (footprint "eagle-import:C0603")
      (libsource (lib "eagle-import") (part "C-EUC0603"))
    )
    (comp (ref "C67")
      (value "10u")
      (footprint "eagle-import:EC1206")
      (libsource (lib "eagle-import") (part "ECAP1206"))
    )
    (comp (ref "C68")
      (value "100n")
      (footprint "eagle-import:C0603")
      (libsource (lib "eagle-import") (part "C-EUC0603"))
    )
    (comp (ref "C69")
      (value "100n")
      (footprint "eagle-import:C0603")
      (libsource (lib "eagle-import") (part "C-EUC0603"))
    )
    (comp (ref "C70")
      (value "100n")
      (footprint "eagle-import:C0603")
      (libsource (lib "eagle-import") (part "C-EUC0603"))
    )
    (comp (ref "C71")
      (value "100n")
      (footprint "eagle-import:C0603")
      (libsource (lib "eagle-import") (part "C-EUC0603"))
    )
    (comp (ref "FB2")
      (value "BLM18AG102SH1D")
      (footprint "eagle-import:BEAD0603")
      (libsource (lib "eagle-import") (part "FERRITE_BEAD0603"))
    )
    (comp (ref "IC15")
      (value "TPD4E001DRLR")
      (footprint "eagle-import:DRL6")
      (libsource (lib "eagle-import") (part "TPD4E001-DRL"))
    )
    (comp (ref "IC16")
      (value "DP83848CVV/NOPB")
      (footprint "eagle-import:PT48")
      (libsource (lib "eagle-import") (part "DP83848CVV/NOPB"))
    )
    (comp (ref "JP9")
      (value "JP2-CUT")
      (footprint "eagle-import:JP2-CUT")
      (libsource (lib "eagle-import") (part "JP2-CUT"))
    )
    (comp (ref "JP10")
      (value "JP2-CUT")
      (footprint "eagle-import:JP2-CUT")
      (libsource (lib "eagle-import") (part "JP2-CUT"))
    )
    (comp (ref "JP11")
      (value "JP2-CUT")
      (footprint "eagle-import:JP2-CUT")
      (libsource (lib "eagle-import") (part "JP2-CUT"))
    )
    (comp (ref "JP12")
      (value "JP2-NOCUT")
      (footprint "eagle-import:JP2-NOCUT")
      (libsource (lib "eagle-import") (part "JP2-NOCUT"))
    )
    (comp (ref "JP13")
      (value "JP2-NOCUT")
      (footprint "eagle-import:JP2-NOCUT")
      (libsource (lib "eagle-import") (part "JP2-NOCUT"))
    )
    (comp (ref "R39")
      (value "1K5")
      (footprint "eagle-import:R0805")
      (libsource (lib "eagle-import") (part "R-EU_R0805"))
    )
    (comp (ref "R40")
      (value "49R9")
      (footprint "eagle-import:R0805")
      (libsource (lib "eagle-import") (part "R-EU_R0805"))
    )
    (comp (ref "R41")
      (value "49R9")
      (footprint "eagle-import:R0805")
      (libsource (lib "eagle-import") (part "R-EU_R0805"))
    )
    (comp (ref "R42")
      (value "2K2")
      (footprint "eagle-import:R0805")
      (libsource (lib "eagle-import") (part "R-EU_R0805"))
    )
    (comp (ref "R43")
      (value "2K2")
      (footprint "eagle-import:R0805")
      (libsource (lib "eagle-import") (part "R-EU_R0805"))
    )
    (comp (ref "R44")
      (value "49R9")
      (footprint "eagle-import:R0805")
      (libsource (lib "eagle-import") (part "R-EU_R0805"))
    )
    (comp (ref "R45")
      (value "2K2")
      (footprint "eagle-import:R0805")
      (libsource (lib "eagle-import") (part "R-EU_R0805"))
    )
    (comp (ref "R46")
      (value "220R")
      (footprint "eagle-import:R0805")
      (libsource (lib "eagle-import") (part "R-EU_R0805"))
    )
    (comp (ref "R47")
      (value "2K2")
      (footprint "eagle-import:R0805")
      (libsource (lib "eagle-import") (part "R-EU_R0805"))
    )
    (comp (ref "R48")
      (value "2K2")
      (footprint "eagle-import:R0805")
      (libsource (lib "eagle-import") (part "R-EU_R0805"))
    )
    (comp (ref "R49")
      (value "49R9")
      (footprint "eagle-import:R0805")
      (libsource (lib "eagle-import") (part "R-EU_R0805"))
    )
    (comp (ref "R50")
      (value "2K2")
      (footprint "eagle-import:R0805")
      (libsource (lib "eagle-import") (part "R-EU_R0805"))
    )
    (comp (ref "R51")
      (value "220R")
      (footprint "eagle-import:R0805")
      (libsource (lib "eagle-import") (part "R-EU_R0805"))
    )
    (comp (ref "R52")
      (value "220R")
      (footprint "eagle-import:R0805")
      (libsource (lib "eagle-import") (part "R-EU_R0805"))
    )
    (comp (ref "R53")
      (value "2K2")
      (footprint "eagle-import:R0805")
      (libsource (lib "eagle-import") (part "R-EU_R0805"))
    )
    (comp (ref "R54")
      (value "2K2")
      (footprint "eagle-import:R0805")
      (libsource (lib "eagle-import") (part "R-EU_R0805"))
    )
    (comp (ref "R55")
      (value "4K87")
      (footprint "eagle-import:R0805")
      (libsource (lib "eagle-import") (part "R-EU_R0805"))
    )
    (comp (ref "R56")
      (value "2K2")
      (footprint "eagle-import:R0805")
      (libsource (lib "eagle-import") (part "R-EU_R0805"))
    )
    (comp (ref "RN1")
      (value "DR1206-33R-4/8")
      (footprint "eagle-import:CAY16")
      (libsource (lib "eagle-import") (part "R_ARRAY4"))
    )
    (comp (ref "RN2")
      (value "DR1206-33R-4/8")
      (footprint "eagle-import:CAY16")
      (libsource (lib "eagle-import") (part "R_ARRAY4"))
    )
    (comp (ref "RN3")
      (value "DR1206-33R-4/8")
      (footprint "eagle-import:CAY16")
      (libsource (lib "eagle-import") (part "R_ARRAY4"))
    )
    (comp (ref "RN4")
      (value "DR1206-33R-4/8")
      (footprint "eagle-import:CAY16")
      (libsource (lib "eagle-import") (part "R_ARRAY4"))
    )
    (comp (ref "SPEED")
      (value "LTST-C170YKT")
      (footprint "eagle-import:LED_0805")
      (libsource (lib "eagle-import") (part "LED0805"))
    )
    (comp (ref "X5")
      (value "LMJTAB881243M-L")
      (footprint "eagle-import:RJ45-TRAFO-LED")
      (libsource (lib "eagle-import") (part "RJ45-TRAFO-LED"))
    )
  )
  (nets
    (net (code "1") (name "+3V3") (class "Default")
      (node (ref "C15") (pin "+") (pinfunction "+_+") (pintype "passive"))
      (node (ref "C38") (pin "1") (pinfunction "1_1") (pintype "passive"))
      (node (ref "C39") (pin "1") (pinfunction "1_1") (pintype "passive"))
      (node (ref "C40") (pin "2") (pinfunction "2_2") (pintype "passive"))
      (node (ref "C41") (pin "1") (pinfunction "1_1") (pintype "passive"))
      (node (ref "C42") (pin "1") (pinfunction "1_1") (pintype "passive"))
      (node (ref "C43") (pin "1") (pinfunction "1_1") (pintype "passive"))
      (node (ref "C44") (pin "1") (pinfunction "1_1") (pintype "passive"))
      (node (ref "C45") (pin "1") (pinfunction "1_1") (pintype "passive"))
      (node (ref "C46") (pin "1") (pinfunction "1_1") (pintype "passive"))
      (node (ref "C5") (pin "1") (pinfunction "1_1") (pintype "passive"))
      (node (ref "C50") (pin "1") (pinfunction "1_1") (pintype "passive"))
      (node (ref "C56") (pin "2") (pinfunction "2_2") (pintype "passive"))
      (node (ref "C57") (pin "2") (pinfunction "2_2") (pintype "passive"))
      (node (ref "C58") (pin "2") (pinfunction "2_2") (pintype "passive"))
      (node (ref "C60") (pin "1") (pinfunction "1_1") (pintype "passive"))
      (node (ref "C70") (pin "1") (pinfunction "1_1") (pintype "passive"))
      (node (ref "C71") (pin "1") (pinfunction "1_1") (pintype "passive"))
      (node (ref "FB2") (pin "P$1") (pinfunction "1_P$1") (pintype "passive"))
      (node (ref "IC13") (pin "6") (pinfunction "VCC_6") (pintype "passive"))
      (node (ref "IC14") (pin "1") (pinfunction "VDD/REF_1") (pintype "passive"))
      (node (ref "IC15") (pin "6") (pinfunction "VCC_6") (pintype "passive"))
      (node (ref "IC16") (pin "32") (pinfunction "IOVDD33-32_32") (pintype "power_in"))
      (node (ref "IC16") (pin "48") (pinfunction "IOVDD33-48_48") (pintype "power_in"))
      (node (ref "IC2") (pin "5") (pinfunction "VDD_5") (pintype "power_in"))
      (node (ref "IC5") (pin "4") (pinfunction "OUT_4") (pintype "passive"))
      (node (ref "IC6") (pin "6") (pinfunction "VCC_6") (pintype "passive"))
      (node (ref "IC7") (pin "1") (pinfunction "VDD-1_1") (pintype "power_in"))
      (node (ref "IC7") (pin "14") (pinfunction "VDD-14_14") (pintype "power_in"))
      (node (ref "IC7") (pin "27") (pinfunction "VDD-27_27") (pintype "power_in"))
      (node (ref "IC7") (pin "3") (pinfunction "VDDQ-3_3") (pintype "power_in"))
      (node (ref "IC7") (pin "43") (pinfunction "VDDQ-43_43") (pintype "power_in"))
      (node (ref "IC7") (pin "49") (pinfunction "VDDQ-49_49") (pintype "power_in"))
      (node (ref "IC7") (pin "9") (pinfunction "VDDQ-9_9") (pintype "power_in"))
      (node (ref "IC8") (pin "8") (pinfunction "VCC_8") (pintype "power_in"))
      (node (ref "J1") (pin "4") (pinfunction "VDD_4") (pintype "power_in"))
      (node (ref "JP2") (pin "2") (pinfunction "2_2") (pintype "passive"))
      (node (ref "JP5") (pin "1") (pinfunction "1_1") (pintype "passive"))
      (node (ref "JP6") (pin "NO") (pinfunction "NO_NO") (pintype "passive"))
      (node (ref "JP8") (pin "NC") (pinfunction "NC_NC") (pintype "passive"))
      (node (ref "LCD1") (pin "4") (pinfunction "VDD_4") (pintype "power_in"))
      (node (ref "R1") (pin "1") (pinfunction "1_1") (pintype "passive"))
      (node (ref "R14") (pin "1") (pinfunction "1_1") (pintype "passive"))
      (node (ref "R15") (pin "1") (pinfunction "1_1") (pintype "passive"))
      (node (ref "R16") (pin "1") (pinfunction "1_1") (pintype "passive"))
      (node (ref "R21") (pin "1") (pinfunction "1_1") (pintype "passive"))
      (node (ref "R22") (pin "1") (pinfunction "1_1") (pintype "passive"))
      (node (ref "R23") (pin "1") (pinfunction "1_1") (pintype "passive"))
      (node (ref "R27") (pin "2") (pinfunction "2_2") (pintype "passive"))
      (node (ref "R31") (pin "2") (pinfunction "2_2") (pintype "passive"))
      (node (ref "R36") (pin "2") (pinfunction "2_2") (pintype "passive"))
      (node (ref "R39") (pin "2") (pinfunction "2_2") (pintype "passive"))
      (node (ref "R43") (pin "1") (pinfunction "1_1") (pintype "passive"))
      (node (ref "R46") (pin "1") (pinfunction "1_1") (pintype "passive"))
      (node (ref "R47") (pin "1") (pinfunction "1_1") (pintype "passive"))
      (node (ref "R48") (pin "1") (pinfunction "1_1") (pintype "passive"))
      (node (ref "R50") (pin "1") (pinfunction "1_1") (pintype "passive"))
      (node (ref "R53") (pin "1") (pinfunction "1_1") (pintype "passive"))
      (node (ref "R54") (pin "1") (pinfunction "1_1") (pintype "passive"))
      (node (ref "R56") (pin "1") (pinfunction "1_1") (pintype "passive"))
      (node (ref "R9") (pin "1") (pinfunction "1_1") (pintype "passive"))
      (node (ref "SW3") (pin "1") (pinfunction "NC_1") (pintype "passive"))
      (node (ref "VBUS") (pin "A") (pinfunction "A_A") (pintype "passive"))
      (node (ref "X1") (pin "7") (pinfunction "1_7") (pintype "passive"))
      (node (ref "X2") (pin "16") (pinfunction "1_16") (pintype "passive"))
      (node (ref "X5") (pin "12") (pinfunction "YELLOW_A_12") (pintype "passive"))
      (node (ref "X5") (pin "9") (pinfunction "GREEN-A_9") (pintype "passive"))
    )
    (net (code "2") (name "+3V3(A)") (class "Default")
      (node (ref "C62") (pin "2") (pinfunction "2_2") (pintype "passive"))
      (node (ref "C64") (pin "2") (pinfunction "2_2") (pintype "passive"))
      (node (ref "C69") (pin "1") (pinfunction "1_1") (pintype "passive"))
      (node (ref "FB2") (pin "P$2") (pinfunction "2_P$2") (pintype "passive"))
      (node (ref "IC16") (pin "22") (pinfunction "AVDD33_22") (pintype "power_in"))
      (node (ref "X5") (pin "3") (pinfunction "CT_3") (pintype "input"))
      (node (ref "X5") (pin "6") (pinfunction "CR_6") (pintype "input"))
    )
    (net (code "3") (name "+5V") (class "Default")
      (node (ref "C13") (pin "1") (pinfunction "+_1") (pintype "passive"))
      (node (ref "C14") (pin "1") (pinfunction "1_1") (pintype "passive"))
      (node (ref "C2") (pin "1") (pinfunction "1_1") (pintype "passive"))
      (node (ref "C47") (pin "1") (pinfunction "1_1") (pintype "passive"))
      (node (ref "C8") (pin "2") (pinfunction "2_2") (pintype "passive"))
      (node (ref "D1") (pin "C") (pinfunction "C_C") (pintype "passive"))
      (node (ref "IC1") (pin "6") (pinfunction "VCC_6") (pintype "passive"))
      (node (ref "IC3") (pin "8") (pinfunction "VSS_8") (pintype "passive"))
      (node (ref "IC5") (pin "3") (pinfunction "IN_3") (pintype "input"))
      (node (ref "IC9") (pin "5") (pinfunction "IN_5") (pintype "input"))
      (node (ref "JP8") (pin "NO") (pinfunction "NO_NO") (pintype "passive"))
      (node (ref "L1") (pin "1") (pinfunction "1_1") (pintype "passive"))
      (node (ref "R24") (pin "1") (pinfunction "1_1") (pintype "passive"))
      (node (ref "X1") (pin "35") (pinfunction "1_35") (pintype "passive"))
      (node (ref "X1") (pin "36") (pinfunction "1_36") (pintype "passive"))
      (node (ref "X2") (pin "5") (pinfunction "1_5") (pintype "passive"))
      (node (ref "X2") (pin "6") (pinfunction "1_6") (pintype "passive"))
    )
    (net (code "4") (name "+12V") (class "Default")
      (node (ref "X1") (pin "37") (pinfunction "1_37") (pintype "passive"))
      (node (ref "X1") (pin "38") (pinfunction "1_38") (pintype "passive"))
      (node (ref "X2") (pin "3") (pinfunction "1_3") (pintype "passive"))
      (node (ref "X2") (pin "4") (pinfunction "1_4") (pintype "passive"))
    )
    (net (code "5") (name "+VAUX") (class "Default")
      (node (ref "JP3") (pin "2") (pinfunction "2_2") (pintype "passive"))
      (node (ref "X1") (pin "5") (pinfunction "1_5") (pintype "passive"))
      (node (ref "X2") (pin "10") (pinfunction "1_10") (pintype "passive"))
    )
    (net (code "12") (name "BOOT0") (class "Default")
      (node (ref "IC4") (pin "166") (pinfunction "BOOT0_166") (pintype "input"))
      (node (ref "R13") (pin "2") (pinfunction "2_2") (pintype "passive"))
      (node (ref "SW3") (pin "2") (pinfunction "COM_2") (pintype "passive"))
    )
    (net (code "13") (name "BYPASS_REG") (class "Default")
      (node (ref "IC4") (pin "48") (pinfunction "BYPASS_REG_48") (pintype "input"))
      (node (ref "R12") (pin "2") (pinfunction "2_2") (pintype "passive"))
    )
    (net (code "14") (name "DAC_OUT1") (class "Default")
      (node (ref "C55") (pin "2") (pinfunction "2_2") (pintype "passive"))
      (node (ref "IC4") (pin "50") (pinfunction "PA4_50") (pintype "bidirectional"))
    )
    (net (code "15") (name "DIN1") (class "Default")
      (node (ref "IC4") (pin "7") (pinfunction "PI8_7") (pintype "bidirectional"))
      (node (ref "R4") (pin "2") (pinfunction "2_2") (pintype "passive"))
    )
    (net (code "16") (name "DIN2") (class "Default")
      (node (ref "IC4") (pin "8") (pinfunction "PC13_8") (pintype "bidirectional"))
      (node (ref "R8") (pin "2") (pinfunction "2_2") (pintype "passive"))
    )
    (net (code "17") (name "DOUT1") (class "Default")
      (node (ref "IC3") (pin "2") (pinfunction "IN1_2") (pintype "input"))
      (node (ref "IC4") (pin "162") (pinfunction "PB4_162") (pintype "bidirectional"))
    )
    (net (code "18") (name "DOUT2") (class "Default")
      (node (ref "IC3") (pin "3") (pinfunction "IN2_3") (pintype "input"))
      (node (ref "IC4") (pin "163") (pinfunction "PB5_163") (pintype "bidirectional"))
    )
    (net (code "19") (name "ENC_A") (class "Default")
      (node (ref "C6") (pin "2") (pinfunction "2_2") (pintype "passive"))
      (node (ref "IC4") (pin "119") (pinfunction "PC6_119") (pintype "bidirectional"))
      (node (ref "R5") (pin "1") (pinfunction "1_1") (pintype "passive"))
    )
    (net (code "20") (name "ENC_B") (class "Default")
      (node (ref "C7") (pin "1") (pinfunction "1_1") (pintype "passive"))
      (node (ref "IC4") (pin "120") (pinfunction "PC7_120") (pintype "bidirectional"))
      (node (ref "R10") (pin "1") (pinfunction "1_1") (pintype "passive"))
    )
    (net (code "21") (name "ENC_SW") (class "Default")
      (node (ref "C3") (pin "2") (pinfunction "2_2") (pintype "passive"))
      (node (ref "IC4") (pin "173") (pinfunction "PI4_173") (pintype "bidirectional"))
      (node (ref "SW2") (pin "E") (pinfunction "2_E") (pintype "passive"))
    )
    (net (code "22") (name "ETH_COL") (class "Default")
      (node (ref "IC4") (pin "47") (pinfunction "PA3_47") (pintype "bidirectional"))
      (node (ref "RN2") (pin "2") (pinfunction "1_2") (pintype "passive"))
    )
    (net (code "23") (name "ETH_CRS") (class "Default")
      (node (ref "IC4") (pin "40") (pinfunction "PA0_40") (pintype "bidirectional"))
      (node (ref "JP9") (pin "1") (pinfunction "1_1") (pintype "passive"))
      (node (ref "RN1") (pin "4") (pinfunction "1_4") (pintype "passive"))
    )
    (net (code "24") (name "ETH_MDC") (class "Default")
      (node (ref "IC16") (pin "31") (pinfunction "MDC_31") (pintype "input"))
      (node (ref "IC4") (pin "33") (pinfunction "PC1_33") (pintype "bidirectional"))
    )
    (net (code "25") (name "ETH_MDIO") (class "Default")
      (node (ref "IC16") (pin "30") (pinfunction "MDIO_30") (pintype "bidirectional"))
      (node (ref "IC4") (pin "42") (pinfunction "PA2_42") (pintype "bidirectional"))
      (node (ref "R39") (pin "1") (pinfunction "1_1") (pintype "passive"))
    )
    (net (code "26") (name "ETH_RXD0") (class "Default")
      (node (ref "IC4") (pin "54") (pinfunction "PC4_54") (pintype "bidirectional"))
      (node (ref "RN2") (pin "3") (pinfunction "1_3") (pintype "passive"))
    )
    (net (code "27") (name "ETH_RXD1") (class "Default")
      (node (ref "IC4") (pin "55") (pinfunction "PC5_55") (pintype "bidirectional"))
      (node (ref "RN2") (pin "4") (pinfunction "1_4") (pintype "passive"))
    )
    (net (code "28") (name "ETH_RXD2") (class "Default")
      (node (ref "IC4") (pin "83") (pinfunction "PH6_83") (pintype "bidirectional"))
      (node (ref "RN3") (pin "1") (pinfunction "1_1") (pintype "passive"))
    )
    (net (code "29") (name "ETH_RXD3") (class "Default")
      (node (ref "IC4") (pin "84") (pinfunction "PH7_84") (pintype "bidirectional"))
      (node (ref "RN3") (pin "2") (pinfunction "1_2") (pintype "passive"))
    )
    (net (code "30") (name "ETH_RX_CLK") (class "Default")
      (node (ref "IC4") (pin "41") (pinfunction "PA1_41") (pintype "bidirectional"))
      (node (ref "RN1") (pin "2") (pinfunction "1_2") (pintype "passive"))
    )
    (net (code "31") (name "ETH_RX_DV") (class "Default")
      (node (ref "IC4") (pin "53") (pinfunction "PA7_53") (pintype "bidirectional"))
      (node (ref "RN1") (pin "3") (pinfunction "1_3") (pintype "passive"))
    )
    (net (code "32") (name "ETH_RX_ERR") (class "Default")
      (node (ref "IC4") (pin "79") (pinfunction "PB10_79") (pintype "bidirectional"))
      (node (ref "JP12") (pin "2") (pinfunction "2_2") (pintype "passive"))
    )
    (net (code "33") (name "ETH_TXD0") (class "Default")
      (node (ref "IC4") (pin "85") (pinfunction "PB12_85") (pintype "bidirectional"))
      (node (ref "RN4") (pin "1") (pinfunction "1_1") (pintype "passive"))
    )
    (net (code "34") (name "ETH_TXD1") (class "Default")
      (node (ref "IC4") (pin "86") (pinfunction "PB13_86") (pintype "bidirectional"))
      (node (ref "RN4") (pin "2") (pinfunction "1_2") (pintype "passive"))
    )
    (net (code "35") (name "ETH_TXD2") (class "Default")
      (node (ref "IC4") (pin "34") (pinfunction "PC2_34") (pintype "bidirectional"))
      (node (ref "RN4") (pin "3") (pinfunction "1_3") (pintype "passive"))
    )
    (net (code "36") (name "ETH_TXD3") (class "Default")
      (node (ref "IC4") (pin "167") (pinfunction "PB8_167") (pintype "bidirectional"))
      (node (ref "RN4") (pin "4") (pinfunction "1_4") (pintype "passive"))
    )
    (net (code "37") (name "ETH_TX_CLK") (class "Default")
      (node (ref "IC4") (pin "35") (pinfunction "PC3_35") (pintype "bidirectional"))
      (node (ref "RN3") (pin "3") (pinfunction "1_3") (pintype "passive"))
    )
    (net (code "38") (name "ETH_TX_EN") (class "Default")
      (node (ref "IC4") (pin "80") (pinfunction "PB11_80") (pintype "bidirectional"))
      (node (ref "RN3") (pin "4") (pinfunction "1_4") (pintype "passive"))
    )
    (net (code "39") (name "FMC_A0") (class "Default")
      (node (ref "IC4") (pin "16") (pinfunction "PF0_16") (pintype "bidirectional"))
      (node (ref "IC7") (pin "23") (pinfunction "A0_23") (pintype "input"))
    )
    (net (code "40") (name "FMC_A1") (class "Default")
      (node (ref "IC4") (pin "17") (pinfunction "PF1_17") (pintype "bidirectional"))
      (node (ref "IC7") (pin "24") (pinfunction "A1_24") (pintype "input"))
    )
    (net (code "41") (name "FMC_A2") (class "Default")
      (node (ref "IC4") (pin "18") (pinfunction "PF2_18") (pintype "bidirectional"))
      (node (ref "IC7") (pin "25") (pinfunction "A2_25") (pintype "input"))
    )
    (net (code "42") (name "FMC_A3") (class "Default")
      (node (ref "IC4") (pin "19") (pinfunction "PF3_19") (pintype "bidirectional"))
      (node (ref "IC7") (pin "26") (pinfunction "A3_26") (pintype "input"))
    )
    (net (code "43") (name "FMC_A4") (class "Default")
      (node (ref "IC4") (pin "20") (pinfunction "PF4_20") (pintype "bidirectional"))
      (node (ref "IC7") (pin "29") (pinfunction "A4_29") (pintype "input"))
    )
    (net (code "44") (name "FMC_A5") (class "Default")
      (node (ref "IC4") (pin "21") (pinfunction "PF5_21") (pintype "bidirectional"))
      (node (ref "IC7") (pin "30") (pinfunction "A5_30") (pintype "input"))
    )
    (net (code "45") (name "FMC_A6") (class "Default")
      (node (ref "IC4") (pin "60") (pinfunction "PF12_60") (pintype "bidirectional"))
      (node (ref "IC7") (pin "31") (pinfunction "A6_31") (pintype "input"))
    )
    (net (code "46") (name "FMC_A7") (class "Default")
      (node (ref "IC4") (pin "63") (pinfunction "PF13_63") (pintype "bidirectional"))
      (node (ref "IC7") (pin "32") (pinfunction "A7_32") (pintype "input"))
    )
    (net (code "47") (name "FMC_A8") (class "Default")
      (node (ref "IC4") (pin "64") (pinfunction "PF14_64") (pintype "bidirectional"))
      (node (ref "IC7") (pin "33") (pinfunction "A8_33") (pintype "input"))
    )
    (net (code "48") (name "FMC_A9") (class "Default")
      (node (ref "IC4") (pin "65") (pinfunction "PF15_65") (pintype "bidirectional"))
      (node (ref "IC7") (pin "34") (pinfunction "A9_34") (pintype "input"))
    )
    (net (code "49") (name "FMC_A10") (class "Default")
      (node (ref "IC4") (pin "66") (pinfunction "PG0_66") (pintype "bidirectional"))
      (node (ref "IC7") (pin "22") (pinfunction "A10/AP_22") (pintype "input"))
    )
    (net (code "50") (name "FMC_A11") (class "Default")
      (node (ref "IC4") (pin "67") (pinfunction "PG1_67") (pintype "bidirectional"))
      (node (ref "IC7") (pin "35") (pinfunction "A11_35") (pintype "input"))
    )
    (net (code "51") (name "FMC_BA0") (class "Default")
      (node (ref "IC4") (pin "112") (pinfunction "PG4_112") (pintype "bidirectional"))
      (node (ref "IC7") (pin "20") (pinfunction "BA0_20") (pintype "input"))
    )
    (net (code "52") (name "FMC_BA1") (class "Default")
      (node (ref "IC4") (pin "113") (pinfunction "PG5_113") (pintype "bidirectional"))
      (node (ref "IC7") (pin "21") (pinfunction "BA1_21") (pintype "input"))
    )
    (net (code "53") (name "FMC_D0") (class "Default")
      (node (ref "IC4") (pin "97") (pinfunction "PD14_97") (pintype "bidirectional"))
      (node (ref "IC7") (pin "2") (pinfunction "DQ0_2") (pintype "bidirectional"))
    )
    (net (code "54") (name "FMC_D1") (class "Default")
      (node (ref "IC4") (pin "98") (pinfunction "PD15_98") (pintype "bidirectional"))
      (node (ref "IC7") (pin "4") (pinfunction "DQ1_4") (pintype "bidirectional"))
    )
    (net (code "55") (name "FMC_D2") (class "Default")
      (node (ref "IC4") (pin "142") (pinfunction "PD0_142") (pintype "bidirectional"))
      (node (ref "IC7") (pin "5") (pinfunction "DQ2_5") (pintype "bidirectional"))
    )
    (net (code "56") (name "FMC_D3") (class "Default")
      (node (ref "IC4") (pin "143") (pinfunction "PD1_143") (pintype "bidirectional"))
      (node (ref "IC7") (pin "7") (pinfunction "DQ3_7") (pintype "bidirectional"))
    )
    (net (code "57") (name "FMC_D4") (class "Default")
      (node (ref "IC4") (pin "68") (pinfunction "PE7_68") (pintype "bidirectional"))
      (node (ref "IC7") (pin "8") (pinfunction "DQ4_8") (pintype "bidirectional"))
    )
    (net (code "58") (name "FMC_D5") (class "Default")
      (node (ref "IC4") (pin "69") (pinfunction "PE8_69") (pintype "bidirectional"))
      (node (ref "IC7") (pin "10") (pinfunction "DQ5_10") (pintype "bidirectional"))
    )
    (net (code "59") (name "FMC_D6") (class "Default")
      (node (ref "IC4") (pin "70") (pinfunction "PE9_70") (pintype "bidirectional"))
      (node (ref "IC7") (pin "11") (pinfunction "DQ6_11") (pintype "bidirectional"))
    )
    (net (code "60") (name "FMC_D7") (class "Default")
      (node (ref "IC4") (pin "73") (pinfunction "PE10_73") (pintype "bidirectional"))
      (node (ref "IC7") (pin "13") (pinfunction "DQ7_13") (pintype "bidirectional"))
    )
    (net (code "61") (name "FMC_D8") (class "Default")
      (node (ref "IC4") (pin "74") (pinfunction "PE11_74") (pintype "bidirectional"))
      (node (ref "IC7") (pin "42") (pinfunction "DQ8_42") (pintype "bidirectional"))
    )
    (net (code "62") (name "FMC_D9") (class "Default")
      (node (ref "IC4") (pin "75") (pinfunction "PE12_75") (pintype "bidirectional"))
      (node (ref "IC7") (pin "44") (pinfunction "DQ9_44") (pintype "bidirectional"))
    )
    (net (code "63") (name "FMC_D10") (class "Default")
      (node (ref "IC4") (pin "76") (pinfunction "PE13_76") (pintype "bidirectional"))
      (node (ref "IC7") (pin "45") (pinfunction "DQ10_45") (pintype "bidirectional"))
    )
    (net (code "64") (name "FMC_D11") (class "Default")
      (node (ref "IC4") (pin "77") (pinfunction "PE14_77") (pintype "bidirectional"))
      (node (ref "IC7") (pin "47") (pinfunction "DQ11_47") (pintype "bidirectional"))
    )
    (net (code "65") (name "FMC_D12") (class "Default")
      (node (ref "IC4") (pin "78") (pinfunction "PE15_78") (pintype "bidirectional"))
      (node (ref "IC7") (pin "48") (pinfunction "DQ12_48") (pintype "bidirectional"))
    )
    (net (code "66") (name "FMC_D13") (class "Default")
      (node (ref "IC4") (pin "89") (pinfunction "PD8_89") (pintype "bidirectional"))
      (node (ref "IC7") (pin "50") (pinfunction "DQ13_50") (pintype "bidirectional"))
    )
    (net (code "67") (name "FMC_D14") (class "Default")
      (node (ref "IC4") (pin "90") (pinfunction "PD9_90") (pintype "bidirectional"))
      (node (ref "IC7") (pin "51") (pinfunction "DQ14_51") (pintype "bidirectional"))
    )
    (net (code "68") (name "FMC_D15") (class "Default")
      (node (ref "IC4") (pin "91") (pinfunction "PD10_91") (pintype "bidirectional"))
      (node (ref "IC7") (pin "53") (pinfunction "DQ15_53") (pintype "bidirectional"))
    )
    (net (code "69") (name "FMC_NBL0") (class "Default")
      (node (ref "IC4") (pin "169") (pinfunction "PE0_169") (pintype "bidirectional"))
      (node (ref "IC7") (pin "15") (pinfunction "LDQM_15") (pintype "input"))
    )
    (net (code "70") (name "FMC_NBL1") (class "Default")
      (node (ref "IC4") (pin "170") (pinfunction "PE1_170") (pintype "bidirectional"))
      (node (ref "IC7") (pin "39") (pinfunction "UDQM_39") (pintype "input"))
    )
    (net (code "71") (name "FMC_SDCKE0") (class "Default")
      (node (ref "IC4") (pin "43") (pinfunction "PH2_43") (pintype "bidirectional"))
      (node (ref "IC7") (pin "37") (pinfunction "CKE_37") (pintype "input"))
    )
    (net (code "72") (name "FMC_SDCLK") (class "Default")
      (node (ref "IC4") (pin "116") (pinfunction "PG8_116") (pintype "bidirectional"))
      (node (ref "IC7") (pin "38") (pinfunction "CLK_38") (pintype "input"))
    )
    (net (code "73") (name "FMC_SDNCAS") (class "Default")
      (node (ref "IC4") (pin "160") (pinfunction "PG15_160") (pintype "bidirectional"))
      (node (ref "IC7") (pin "17") (pinfunction "~{CAS}_17") (pintype "input"))
    )
    (net (code "74") (name "FMC_SDNE0") (class "Default")
      (node (ref "IC4") (pin "44") (pinfunction "PH3_44") (pintype "bidirectional"))
      (node (ref "IC7") (pin "19") (pinfunction "~{CS}_19") (pintype "input"))
      (node (ref "R23") (pin "2") (pinfunction "2_2") (pintype "passive"))
    )
    (net (code "75") (name "FMC_SDNRAS") (class "Default")
      (node (ref "IC4") (pin "59") (pinfunction "PF11_59") (pintype "bidirectional"))
      (node (ref "IC7") (pin "18") (pinfunction "~{RAS}_18") (pintype "input"))
    )
    (net (code "76") (name "FMC_SDNWE") (class "Default")
      (node (ref "IC4") (pin "46") (pinfunction "PH5_46") (pintype "bidirectional"))
      (node (ref "IC7") (pin "16") (pinfunction "~{WE}_16") (pintype "input"))
    )
    (net (code "77") (name "GND") (class "Default")
      (node (ref "B1") (pin "2") (pinfunction "-_2") (pintype "passive"))
      (node (ref "C1") (pin "2") (pinfunction "2_2") (pintype "passive"))
      (node (ref "C10") (pin "2") (pinfunction "2_2") (pintype "passive"))
      (node (ref "C11") (pin "1") (pinfunction "1_1") (pintype "passive"))
      (node (ref "C12") (pin "2") (pinfunction "2_2") (pintype "passive"))
      (node (ref "C13") (pin "2") (pinfunction "-_2") (pintype "passive"))
      (node (ref "C14") (pin "2") (pinfunction "2_2") (pintype "passive"))
      (node (ref "C15") (pin "-") (pinfunction "-_-") (pintype "passive"))
      (node (ref "C16") (pin "2") (pinfunction "2_2") (pintype "passive"))
      (node (ref "C17") (pin "2") (pinfunction "2_2") (pintype "passive"))
      (node (ref "C18") (pin "2") (pinfunction "2_2") (pintype "passive"))
      (node (ref "C19") (pin "2") (pinfunction "2_2") (pintype "passive"))
      (node (ref "C2") (pin "2") (pinfunction "2_2") (pintype "passive"))
      (node (ref "C20") (pin "2") (pinfunction "2_2") (pintype "passive"))
      (node (ref "C21") (pin "2") (pinfunction "2_2") (pintype "passive"))
      (node (ref "C22") (pin "-") (pinfunction "-_-") (pintype "passive"))
      (node (ref "C23") (pin "2") (pinfunction "2_2") (pintype "passive"))
      (node (ref "C24") (pin "2") (pinfunction "2_2") (pintype "passive"))
      (node (ref "C25") (pin "2") (pinfunction "2_2") (pintype "passive"))
      (node (ref "C26") (pin "2") (pinfunction "2_2") (pintype "passive"))
      (node (ref "C27") (pin "2") (pinfunction "2_2") (pintype "passive"))
      (node (ref "C28") (pin "2") (pinfunction "2_2") (pintype "passive"))
      (node (ref "C29") (pin "2") (pinfunction "2_2") (pintype "passive"))
      (node (ref "C3") (pin "1") (pinfunction "1_1") (pintype "passive"))
      (node (ref "C30") (pin "2") (pinfunction "2_2") (pintype "passive"))
      (node (ref "C31") (pin "2") (pinfunction "2_2") (pintype "passive"))
      (node (ref "C32") (pin "2") (pinfunction "2_2") (pintype "passive"))
      (node (ref "C33") (pin "2") (pinfunction "2_2") (pintype "passive"))
      (node (ref "C34") (pin "2") (pinfunction "2_2") (pintype "passive"))
      (node (ref "C35") (pin "2") (pinfunction "2_2") (pintype "passive"))
      (node (ref "C36") (pin "2") (pinfunction "2_2") (pintype "passive"))
      (node (ref "C37") (pin "2") (pinfunction "2_2") (pintype "passive"))
      (node (ref "C38") (pin "2") (pinfunction "2_2") (pintype "passive"))
      (node (ref "C39") (pin "2") (pinfunction "2_2") (pintype "passive"))
      (node (ref "C4") (pin "1") (pinfunction "1_1") (pintype "passive"))
      (node (ref "C40") (pin "1") (pinfunction "1_1") (pintype "passive"))
      (node (ref "C41") (pin "2") (pinfunction "2_2") (pintype "passive"))
      (node (ref "C42") (pin "2") (pinfunction "2_2") (pintype "passive"))
      (node (ref "C43") (pin "2") (pinfunction "2_2") (pintype "passive"))
      (node (ref "C44") (pin "2") (pinfunction "2_2") (pintype "passive"))
      (node (ref "C45") (pin "2") (pinfunction "2_2") (pintype "passive"))
      (node (ref "C46") (pin "2") (pinfunction "2_2") (pintype "passive"))
      (node (ref "C47") (pin "2") (pinfunction "2_2") (pintype "passive"))
      (node (ref "C48") (pin "2") (pinfunction "2_2") (pintype "passive"))
      (node (ref "C49") (pin "-") (pinfunction "-_-") (pintype "passive"))
      (node (ref "C5") (pin "2") (pinfunction "2_2") (pintype "passive"))
      (node (ref "C50") (pin "2") (pinfunction "2_2") (pintype "passive"))
      (node (ref "C51") (pin "2") (pinfunction "2_2") (pintype "passive"))
      (node (ref "C52") (pin "1") (pinfunction "1_1") (pintype "passive"))
      (node (ref "C53") (pin "1") (pinfunction "1_1") (pintype "passive"))
      (node (ref "C54") (pin "2") (pinfunction "2_2") (pintype "passive"))
      (node (ref "C56") (pin "1") (pinfunction "1_1") (pintype "passive"))
      (node (ref "C57") (pin "1") (pinfunction "1_1") (pintype "passive"))
      (node (ref "C58") (pin "1") (pinfunction "1_1") (pintype "passive"))
      (node (ref "C59") (pin "1") (pinfunction "1_1") (pintype "passive"))
      (node (ref "C6") (pin "1") (pinfunction "1_1") (pintype "passive"))
      (node (ref "C60") (pin "2") (pinfunction "2_2") (pintype "passive"))
      (node (ref "C61") (pin "2") (pinfunction "2_2") (pintype "passive"))
      (node (ref "C62") (pin "1") (pinfunction "1_1") (pintype "passive"))
      (node (ref "C63") (pin "2") (pinfunction "2_2") (pintype "passive"))
      (node (ref "C64") (pin "1") (pinfunction "1_1") (pintype "passive"))
      (node (ref "C65") (pin "2") (pinfunction "2_2") (pintype "passive"))
      (node (ref "C66") (pin "2") (pinfunction "2_2") (pintype "passive"))
      (node (ref "C67") (pin "-") (pinfunction "-_-") (pintype "passive"))
      (node (ref "C68") (pin "2") (pinfunction "2_2") (pintype "passive"))
      (node (ref "C69") (pin "2") (pinfunction "2_2") (pintype "passive"))
      (node (ref "C7") (pin "2") (pinfunction "2_2") (pintype "passive"))
      (node (ref "C70") (pin "2") (pinfunction "2_2") (pintype "passive"))
      (node (ref "C71") (pin "2") (pinfunction "2_2") (pintype "passive"))
      (node (ref "C8") (pin "1") (pinfunction "1_1") (pintype "passive"))
      (node (ref "C9") (pin "1") (pinfunction "1_1") (pintype "passive"))
      (node (ref "D1") (pin "A") (pinfunction "A_A") (pintype "passive"))
      (node (ref "IC1") (pin "3") (pinfunction "GND_3") (pintype "power_in"))
      (node (ref "IC10") (pin "2") (pinfunction "GND_2") (pintype "power_in"))
      (node (ref "IC11") (pin "3") (pinfunction "GND_3") (pintype "power_in"))
      (node (ref "IC12") (pin "7") (pinfunction "GND_7") (pintype "passive"))
      (node (ref "IC12") (pin "TP") (pinfunction "TP_TP") (pintype "passive"))
      (node (ref "IC13") (pin "3") (pinfunction "GND_3") (pintype "power_in"))
      (node (ref "IC14") (pin "13") (pinfunction "A1_13") (pintype "input"))
      (node (ref "IC14") (pin "14") (pinfunction "A0_14") (pintype "input"))
      (node (ref "IC14") (pin "6") (pinfunction "GND_6") (pintype "passive"))
      (node (ref "IC15") (pin "3") (pinfunction "GND_3") (pintype "power_in"))
      (node (ref "IC16") (pin "15") (pinfunction "AGND-15_15") (pintype "power_in"))
      (node (ref "IC16") (pin "19") (pinfunction "AGND-19_19") (pintype "power_in"))
      (node (ref "IC16") (pin "35") (pinfunction "IOGND-35_35") (pintype "power_in"))
      (node (ref "IC16") (pin "36") (pinfunction "DGND_36") (pintype "power_in"))
      (node (ref "IC16") (pin "47") (pinfunction "IOGND-47_47") (pintype "power_in"))
      (node (ref "IC2") (pin "2") (pinfunction "VSS_2") (pintype "power_in"))
      (node (ref "IC3") (pin "6") (pinfunction "GND_6") (pintype "passive"))
      (node (ref "IC4") (pin "103") (pinfunction "VSSDSI_2_103") (pintype "power_in"))
      (node (ref "IC4") (pin "109") (pinfunction "VSSDSI_109") (pintype "power_in"))
      (node (ref "IC4") (pin "117") (pinfunction "VSS_7_117") (pintype "power_in"))
      (node (ref "IC4") (pin "130") (pinfunction "VSS_8_130") (pintype "power_in"))
      (node (ref "IC4") (pin "135") (pinfunction "VSS_9_135") (pintype "power_in"))
      (node (ref "IC4") (pin "14") (pinfunction "VSS_2_14") (pintype "power_in"))
      (node (ref "IC4") (pin "148") (pinfunction "VSS_10_148") (pintype "power_in"))
      (node (ref "IC4") (pin "158") (pinfunction "VSS_158") (pintype "power_in"))
      (node (ref "IC4") (pin "22") (pinfunction "VSS_3_22") (pintype "power_in"))
      (node (ref "IC4") (pin "37") (pinfunction "VSSA_37") (pintype "power_in"))
      (node (ref "IC4") (pin "61") (pinfunction "VSS_4_61") (pintype "power_in"))
      (node (ref "IC4") (pin "71") (pinfunction "VSS_5_71") (pintype "power_in"))
      (node (ref "IC4") (pin "95") (pinfunction "VSS_6_95") (pintype "power_in"))
      (node (ref "IC5") (pin "1") (pinfunction "ADJ_1") (pintype "input"))
      (node (ref "IC6") (pin "3") (pinfunction "GND_3") (pintype "power_in"))
      (node (ref "IC7") (pin "12") (pinfunction "GNDQ-12_12") (pintype "power_in"))
      (node (ref "IC7") (pin "28") (pinfunction "GND-28_28") (pintype "power_in"))
      (node (ref "IC7") (pin "41") (pinfunction "GND_41") (pintype "power_in"))
      (node (ref "IC7") (pin "46") (pinfunction "GNDQ-46_46") (pintype "power_in"))
      (node (ref "IC7") (pin "52") (pinfunction "GNDQ-52_52") (pintype "power_in"))
      (node (ref "IC7") (pin "54") (pinfunction "GND-54_54") (pintype "power_in"))
      (node (ref "IC7") (pin "6") (pinfunction "GNDQ-6_6") (pintype "power_in"))
      (node (ref "IC8") (pin "1") (pinfunction "A0_1") (pintype "input"))
      (node (ref "IC8") (pin "2") (pinfunction "A1_2") (pintype "input"))
      (node (ref "IC8") (pin "3") (pinfunction "A2_3") (pintype "input"))
      (node (ref "IC8") (pin "4") (pinfunction "GND_4") (pintype "passive"))
      (node (ref "IC8") (pin "7") (pinfunction "WP_7") (pintype "input"))
      (node (ref "IC9") (pin "2") (pinfunction "GND_2") (pintype "power_in"))
      (node (ref "J1") (pin "6") (pinfunction "VSS_6") (pintype "power_in"))
      (node (ref "J1") (pin "S") (pinfunction "SH_S") (pintype "passive"))
      (node (ref "J1") (pin "SW2") (pinfunction "SW2_SW2") (pintype "passive"))
      (node (ref "J2") (pin "5") (pinfunction "GND_5") (pintype "passive"))
      (node (ref "JP1") (pin "1") (pinfunction "1_1") (pintype "passive"))
      (node (ref "JP6") (pin "NC") (pinfunction "NC_NC") (pintype "passive"))
      (node (ref "JP7") (pin "NC") (pinfunction "NC_NC") (pintype "passive"))
      (node (ref "LCD1") (pin "29") (pinfunction "GND-29_29") (pintype "power_in"))
      (node (ref "LCD1") (pin "3") (pinfunction "GND-3_3") (pintype "power_in"))
      (node (ref "Q1") (pin "E") (pinfunction "E_E") (pintype "passive"))
      (node (ref "R12") (pin "1") (pinfunction "1_1") (pintype "passive"))
      (node (ref "R13") (pin "1") (pinfunction "1_1") (pintype "passive"))
      (node (ref "R18") (pin "1") (pinfunction "1_1") (pintype "passive"))
      (node (ref "R26") (pin "2") (pinfunction "2_2") (pintype "passive"))
      (node (ref "R42") (pin "1") (pinfunction "1_1") (pintype "passive"))
      (node (ref "R45") (pin "1") (pinfunction "1_1") (pintype "passive"))
      (node (ref "R55") (pin "1") (pinfunction "1_1") (pintype "passive"))
      (node (ref "SW1") (pin "2") (pinfunction "2_2") (pintype "passive"))
      (node (ref "SW2") (pin "C") (pinfunction "C_C") (pintype "passive"))
      (node (ref "SW2") (pin "D") (pinfunction "1_D") (pintype "passive"))
      (node (ref "SW2") (pin "GND1") (pinfunction "C_GND1") (pintype "passive"))
      (node (ref "SW2") (pin "GND2") (pinfunction "C_GND2") (pintype "passive"))
      (node (ref "TP1") (pin "1") (pinfunction "P$1_1") (pintype "bidirectional"))
      (node (ref "X1") (pin "1") (pinfunction "1_1") (pintype "passive"))
      (node (ref "X1") (pin "15") (pinfunction "1_15") (pintype "passive"))
      (node (ref "X1") (pin "16") (pinfunction "1_16") (pintype "passive"))
      (node (ref "X1") (pin "2") (pinfunction "1_2") (pintype "passive"))
      (node (ref "X1") (pin "29") (pinfunction "1_29") (pintype "passive"))
      (node (ref "X1") (pin "30") (pinfunction "1_30") (pintype "passive"))
      (node (ref "X1") (pin "34") (pinfunction "1_34") (pintype "passive"))
      (node (ref "X1") (pin "39") (pinfunction "1_39") (pintype "passive"))
      (node (ref "X1") (pin "40") (pinfunction "1_40") (pintype "passive"))
      (node (ref "X2") (pin "7") (pinfunction "1_7") (pintype "passive"))
      (node (ref "X2") (pin "8") (pinfunction "1_8") (pintype "passive"))
      (node (ref "X2") (pin "9") (pinfunction "1_9") (pintype "passive"))
      (node (ref "X3") (pin "3") (pinfunction "1_3") (pintype "passive"))
      (node (ref "X4") (pin "3") (pinfunction "S_3") (pintype "passive"))
      (node (ref "X5") (pin "4") (pinfunction "GND_4") (pintype "passive"))
      (node (ref "X5") (pin "5") (pinfunction "GND_5") (pintype "passive"))
      (node (ref "ZD1") (pin "A") (pinfunction "A_A") (pintype "passive"))
      (node (ref "ZD2") (pin "A") (pinfunction "A_A") (pintype "passive"))
    )
    (net (code "78") (name "I2C1_SCL") (class "Default")
      (node (ref "IC14") (pin "12") (pinfunction "SCL_12") (pintype "bidirectional"))
      (node (ref "IC4") (pin "164") (pinfunction "PB6_164") (pintype "bidirectional"))
      (node (ref "IC8") (pin "6") (pinfunction "SCL_6") (pintype "bidirectional"))
      (node (ref "R15") (pin "2") (pinfunction "2_2") (pintype "passive"))
      (node (ref "X1") (pin "12") (pinfunction "1_12") (pintype "passive"))
      (node (ref "X2") (pin "13") (pinfunction "1_13") (pintype "passive"))
    )
    (net (code "79") (name "I2C1_SDA") (class "Default")
      (node (ref "IC14") (pin "11") (pinfunction "SDA_11") (pintype "bidirectional"))
      (node (ref "IC4") (pin "165") (pinfunction "PB7_165") (pintype "bidirectional"))
      (node (ref "IC8") (pin "5") (pinfunction "SDA_5") (pintype "bidirectional"))
      (node (ref "R16") (pin "2") (pinfunction "2_2") (pintype "passive"))
      (node (ref "X1") (pin "14") (pinfunction "1_14") (pintype "passive"))
      (node (ref "X2") (pin "14") (pinfunction "1_14") (pintype "passive"))
    )
    (net (code "80") (name "IRQ_TOUCH") (class "Default")
      (node (ref "IC14") (pin "10") (pinfunction "~{PENIRQ}_10") (pintype "output"))
      (node (ref "IC4") (pin "151") (pinfunction "PD7_151") (pintype "bidirectional"))
    )
    (net (code "81") (name "LCD_DISP") (class "Default")
      (node (ref "LCD1") (pin "31") (pinfunction "DISP_31") (pintype "input"))
      (node (ref "R31") (pin "1") (pinfunction "1_1") (pintype "passive"))
    )
    (net (code "82") (name "LED_ACT") (class "Default")
      (node (ref "IC16") (pin "26") (pinfunction "AN_EN(LED_ACT/COL)_26") (pintype "output"))
      (node (ref "R43") (pin "2") (pinfunction "2_2") (pintype "passive"))
      (node (ref "R51") (pin "2") (pinfunction "2_2") (pintype "passive"))
    )
    (net (code "83") (name "LED_LINK") (class "Default")
      (node (ref "IC16") (pin "28") (pinfunction "AN_0(LED_LINK)_28") (pintype "output"))
      (node (ref "R50") (pin "2") (pinfunction "2_2") (pintype "passive"))
      (node (ref "R52") (pin "2") (pinfunction "2_2") (pintype "passive"))
    )
    (net (code "84") (name "LED_SPEED") (class "Default")
      (node (ref "IC16") (pin "27") (pinfunction "AN_1(LED_SPEED)_27") (pintype "output"))
      (node (ref "R48") (pin "2") (pinfunction "2_2") (pintype "passive"))
      (node (ref "SPEED") (pin "C") (pinfunction "C_C") (pintype "passive"))
    )
    (net (code "85") (name "LTDC_B2") (class "Default")
      (node (ref "IC4") (pin "150") (pinfunction "PD6_150") (pintype "bidirectional"))
      (node (ref "LCD1") (pin "23") (pinfunction "B2_23") (pintype "input"))
    )
    (net (code "86") (name "LTDC_B3") (class "Default")
      (node (ref "IC4") (pin "154") (pinfunction "PG11_154") (pintype "bidirectional"))
      (node (ref "LCD1") (pin "24") (pinfunction "B3_24") (pintype "input"))
    )
    (net (code "87") (name "LTDC_B4") (class "Default")
      (node (ref "IC4") (pin "155") (pinfunction "PG12_155") (pintype "bidirectional"))
      (node (ref "LCD1") (pin "25") (pinfunction "B4_25") (pintype "input"))
    )
    (net (code "88") (name "LTDC_B5") (class "Default")
      (node (ref "IC4") (pin "174") (pinfunction "PI5_174") (pintype "bidirectional"))
      (node (ref "LCD1") (pin "26") (pinfunction "B5_26") (pintype "input"))
    )
    (net (code "89") (name "LTDC_B6") (class "Default")
      (node (ref "IC4") (pin "175") (pinfunction "PI6_175") (pintype "bidirectional"))
      (node (ref "LCD1") (pin "27") (pinfunction "B6_27") (pintype "input"))
    )
    (net (code "90") (name "LTDC_B7") (class "Default")
      (node (ref "IC4") (pin "176") (pinfunction "PI7_176") (pintype "bidirectional"))
      (node (ref "LCD1") (pin "28") (pinfunction "B7_28") (pintype "input"))
    )
    (net (code "91") (name "LTDC_CLK") (class "Default")
      (node (ref "IC4") (pin "115") (pinfunction "PG7_115") (pintype "bidirectional"))
      (node (ref "LCD1") (pin "30") (pinfunction "CLK_30") (pintype "input"))
    )
    (net (code "92") (name "LTDC_DE") (class "Default")
      (node (ref "IC4") (pin "28") (pinfunction "PF10_28") (pintype "bidirectional"))
      (node (ref "LCD1") (pin "34") (pinfunction "DE/NC2_34") (pintype "passive"))
    )
    (net (code "93") (name "LTDC_G2") (class "Default")
      (node (ref "IC4") (pin "52") (pinfunction "PA6_52") (pintype "bidirectional"))
      (node (ref "LCD1") (pin "15") (pinfunction "G2_15") (pintype "input"))
    )
    (net (code "94") (name "LTDC_G3") (class "Default")
      (node (ref "IC4") (pin "153") (pinfunction "PG10_153") (pintype "bidirectional"))
      (node (ref "LCD1") (pin "16") (pinfunction "G3_16") (pintype "input"))
    )
    (net (code "95") (name "LTDC_G4") (class "Default")
      (node (ref "IC4") (pin "45") (pinfunction "PH4_45") (pintype "bidirectional"))
      (node (ref "LCD1") (pin "17") (pinfunction "G4_17") (pintype "input"))
    )
    (net (code "96") (name "LTDC_G5") (class "Default")
      (node (ref "IC4") (pin "132") (pinfunction "PI0_132") (pintype "bidirectional"))
      (node (ref "LCD1") (pin "18") (pinfunction "G5_18") (pintype "input"))
    )
    (net (code "97") (name "LTDC_G6") (class "Default")
      (node (ref "IC4") (pin "13") (pinfunction "PI11_13") (pintype "bidirectional"))
      (node (ref "LCD1") (pin "19") (pinfunction "G6_19") (pintype "input"))
    )
    (net (code "98") (name "LTDC_G7") (class "Default")
      (node (ref "IC4") (pin "145") (pinfunction "PD3_145") (pintype "bidirectional"))
      (node (ref "LCD1") (pin "20") (pinfunction "G7_20") (pintype "input"))
    )
    (net (code "99") (name "LTDC_HSYNC") (class "Default")
      (node (ref "IC4") (pin "12") (pinfunction "PI10_12") (pintype "bidirectional"))
      (node (ref "LCD1") (pin "32") (pinfunction "HSYNC_32") (pintype "input"))
    )
    (net (code "100") (name "LTDC_R2") (class "Default")
      (node (ref "IC4") (pin "139") (pinfunction "PC10_139") (pintype "bidirectional"))
      (node (ref "LCD1") (pin "7") (pinfunction "R2_7") (pintype "input"))
    )
    (net (code "101") (name "LTDC_R3") (class "Default")
      (node (ref "IC4") (pin "56") (pinfunction "PB0_56") (pintype "bidirectional"))
      (node (ref "LCD1") (pin "8") (pinfunction "R3_8") (pintype "input"))
    )
    (net (code "102") (name "LTDC_R4") (class "Default")
      (node (ref "IC4") (pin "51") (pinfunction "PA5_51") (pintype "bidirectional"))
      (node (ref "LCD1") (pin "9") (pinfunction "R4_9") (pintype "input"))
    )
    (net (code "103") (name "LTDC_R5") (class "Default")
      (node (ref "IC4") (pin "32") (pinfunction "PC0_32") (pintype "bidirectional"))
      (node (ref "LCD1") (pin "10") (pinfunction "R5_10") (pintype "input"))
    )
    (net (code "104") (name "LTDC_R6") (class "Default")
      (node (ref "IC4") (pin "57") (pinfunction "PB1_57") (pintype "bidirectional"))
      (node (ref "LCD1") (pin "11") (pinfunction "R6_11") (pintype "input"))
    )
    (net (code "105") (name "LTDC_R7") (class "Default")
      (node (ref "IC4") (pin "114") (pinfunction "PG6_114") (pintype "bidirectional"))
      (node (ref "LCD1") (pin "12") (pinfunction "R7_12") (pintype "input"))
    )
    (net (code "106") (name "LTDC_VSYNC") (class "Default")
      (node (ref "IC4") (pin "11") (pinfunction "PI9_11") (pintype "bidirectional"))
      (node (ref "LCD1") (pin "33") (pinfunction "VSYNC_33") (pintype "input"))
    )
    (net (code "107") (name "MCLK_25") (class "Default")
      (node (ref "IC4") (pin "122") (pinfunction "PC9_122") (pintype "bidirectional"))
      (node (ref "RN1") (pin "1") (pinfunction "1_1") (pintype "passive"))
    )
    (net (code "108") (name "Net-(B1-+-Pad1)") (class "Default")
      (node (ref "B1") (pin "1") (pinfunction "+_1") (pintype "passive"))
      (node (ref "B1") (pin "3") (pinfunction "+_3") (pintype "passive"))
      (node (ref "JP3") (pin "1") (pinfunction "1_1") (pintype "passive"))
      (node (ref "JP4") (pin "NC") (pinfunction "NC_NC") (pintype "passive"))
    )
    (net (code "109") (name "Net-(C54-Pad1)") (class "Default")
      (node (ref "C54") (pin "1") (pinfunction "1_1") (pintype "passive"))
      (node (ref "R34") (pin "2") (pinfunction "2_2") (pintype "passive"))
    )
    (net (code "110") (name "Net-(C55-Pad1)") (class "Default")
      (node (ref "C55") (pin "1") (pinfunction "1_1") (pintype "passive"))
      (node (ref "R35") (pin "2") (pinfunction "2_2") (pintype "passive"))
    )
    (net (code "111") (name "Net-(C61-Pad1)") (class "Default")
      (node (ref "C61") (pin "1") (pinfunction "1_1") (pintype "passive"))
      (node (ref "R40") (pin "1") (pinfunction "1_1") (pintype "passive"))
      (node (ref "R41") (pin "2") (pinfunction "2_2") (pintype "passive"))
    )
    (net (code "112") (name "Net-(C63-Pad1)") (class "Default")
      (node (ref "C63") (pin "1") (pinfunction "1_1") (pintype "passive"))
      (node (ref "R44") (pin "1") (pinfunction "1_1") (pintype "passive"))
      (node (ref "R49") (pin "2") (pinfunction "2_2") (pintype "passive"))
    )
    (net (code "113") (name "Net-(F1-P$1)") (class "Default")
      (node (ref "F1") (pin "1") (pinfunction "P$1_1") (pintype "bidirectional"))
      (node (ref "X3") (pin "4") (pinfunction "1_4") (pintype "passive"))
    )
    (net (code "114") (name "Net-(F1-P$2)") (class "Default")
      (node (ref "F1") (pin "2") (pinfunction "P$2_2") (pintype "bidirectional"))
      (node (ref "IC1") (pin "4") (pinfunction "IO3_4") (pintype "bidirectional"))
      (node (ref "IC3") (pin "7") (pinfunction "OUT1_7") (pintype "output"))
      (node (ref "ZD1") (pin "C") (pinfunction "C_C") (pintype "passive"))
    )
    (net (code "115") (name "Net-(F2-P$1)") (class "Default")
      (node (ref "F2") (pin "1") (pinfunction "P$1_1") (pintype "bidirectional"))
      (node (ref "X3") (pin "5") (pinfunction "1_5") (pintype "passive"))
    )
    (net (code "116") (name "Net-(F2-P$2)") (class "Default")
      (node (ref "F2") (pin "2") (pinfunction "P$2_2") (pintype "bidirectional"))
      (node (ref "IC1") (pin "5") (pinfunction "IO4_5") (pintype "bidirectional"))
      (node (ref "IC3") (pin "5") (pinfunction "OUT2_5") (pintype "output"))
      (node (ref "ZD2") (pin "C") (pinfunction "C_C") (pintype "passive"))
    )
    (net (code "117") (name "Net-(IC1-IO1)") (class "Default")
      (node (ref "IC1") (pin "1") (pinfunction "IO1_1") (pintype "bidirectional"))
      (node (ref "IC2") (pin "1") (pinfunction "I_1") (pintype "input"))
      (node (ref "R3") (pin "2") (pinfunction "2_2") (pintype "passive"))
    )
    (net (code "118") (name "Net-(IC1-IO2)") (class "Default")
      (node (ref "IC1") (pin "2") (pinfunction "IO2_2") (pintype "bidirectional"))
      (node (ref "IC2") (pin "3") (pinfunction "I_3") (pintype "input"))
      (node (ref "R7") (pin "2") (pinfunction "2_2") (pintype "passive"))
    )
    (net (code "119") (name "Net-(IC2A-O)") (class "Default")
      (node (ref "IC2") (pin "6") (pinfunction "O_6") (pintype "output"))
      (node (ref "R4") (pin "1") (pinfunction "1_1") (pintype "passive"))
    )
    (net (code "120") (name "Net-(IC2B-O)") (class "Default")
      (node (ref "IC2") (pin "4") (pinfunction "O_4") (pintype "output"))
      (node (ref "R8") (pin "1") (pinfunction "1_1") (pintype "passive"))
    )
    (net (code "121") (name "Net-(IC4D-VCAPDSI)") (class "Default")
      (node (ref "IC4") (pin "100") (pinfunction "VCAPDSI_100") (pintype "power_in"))
      (node (ref "IC4") (pin "106") (pinfunction "VDD12DSI_106") (pintype "power_in"))
    )
    (net (code "122") (name "Net-(IC10-SW)") (class "Default")
      (node (ref "D2") (pin "A") (pinfunction "A_A") (pintype "passive"))
      (node (ref "IC10") (pin "1") (pinfunction "SW_1") (pintype "output"))
      (node (ref "L1") (pin "2") (pinfunction "2_2") (pintype "passive"))
    )
    (net (code "123") (name "Net-(IC10-VIN)") (class "Default")
      (node (ref "IC10") (pin "5") (pinfunction "VIN_5") (pintype "input"))
      (node (ref "R24") (pin "2") (pinfunction "2_2") (pintype "passive"))
    )
    (net (code "124") (name "Net-(IC12-BYPASS)") (class "Default")
      (node (ref "C59") (pin "2") (pinfunction "2_2") (pintype "passive"))
      (node (ref "IC12") (pin "2") (pinfunction "BYPASS_2") (pintype "input"))
    )
    (net (code "125") (name "Net-(IC12-IN+)") (class "Default")
      (node (ref "IC12") (pin "3") (pinfunction "IN+_3") (pintype "input"))
      (node (ref "R32") (pin "2") (pinfunction "2_2") (pintype "passive"))
      (node (ref "R34") (pin "1") (pinfunction "1_1") (pintype "passive"))
    )
    (net (code "126") (name "Net-(IC12-IN-)") (class "Default")
      (node (ref "IC12") (pin "4") (pinfunction "IN-_4") (pintype "input"))
      (node (ref "R35") (pin "1") (pinfunction "1_1") (pintype "passive"))
      (node (ref "R37") (pin "2") (pinfunction "2_2") (pintype "passive"))
    )
    (net (code "127") (name "Net-(IC12-VDD)") (class "Default")
      (node (ref "C53") (pin "2") (pinfunction "2_2") (pintype "passive"))
      (node (ref "IC12") (pin "6") (pinfunction "VDD_6") (pintype "power_in"))
      (node (ref "JP8") (pin "COM") (pinfunction "COM_COM") (pintype "passive"))
    )
    (net (code "128") (name "Net-(IC12-VO+)") (class "Default")
      (node (ref "IC12") (pin "5") (pinfunction "VO+_5") (pintype "output"))
      (node (ref "R38") (pin "1") (pinfunction "1_1") (pintype "passive"))
      (node (ref "SP1") (pin "+") (pinfunction "+_+") (pintype "passive"))
    )
    (net (code "129") (name "Net-(IC12-VO-)") (class "Default")
      (node (ref "IC12") (pin "8") (pinfunction "VO-_8") (pintype "output"))
      (node (ref "R33") (pin "1") (pinfunction "1_1") (pintype "passive"))
      (node (ref "SP1") (pin "-") (pinfunction "-_-") (pintype "passive"))
    )
    (net (code "130") (name "Net-(IC12-~{SHDN})") (class "Default")
      (node (ref "IC12") (pin "1") (pinfunction "~{SHDN}_1") (pintype "input"))
      (node (ref "R36") (pin "1") (pinfunction "1_1") (pintype "passive"))
    )
    (net (code "131") (name "Net-(IC15-IO1)") (class "Default")
      (node (ref "IC15") (pin "1") (pinfunction "IO1_1") (pintype "bidirectional"))
      (node (ref "IC16") (pin "17") (pinfunction "TD+_17") (pintype "bidirectional"))
      (node (ref "R40") (pin "2") (pinfunction "2_2") (pintype "passive"))
      (node (ref "X5") (pin "1") (pinfunction "TD+_1") (pintype "input"))
    )
    (net (code "132") (name "Net-(IC15-IO2)") (class "Default")
      (node (ref "IC15") (pin "2") (pinfunction "IO2_2") (pintype "bidirectional"))
      (node (ref "IC16") (pin "16") (pinfunction "TD-_16") (pintype "bidirectional"))
      (node (ref "R41") (pin "1") (pinfunction "1_1") (pintype "passive"))
      (node (ref "X5") (pin "2") (pinfunction "TD-_2") (pintype "input"))
    )
    (net (code "133") (name "Net-(IC15-IO3)") (class "Default")
      (node (ref "IC15") (pin "4") (pinfunction "IO3_4") (pintype "bidirectional"))
      (node (ref "IC16") (pin "14") (pinfunction "RD+_14") (pintype "bidirectional"))
      (node (ref "R44") (pin "2") (pinfunction "2_2") (pintype "passive"))
      (node (ref "X5") (pin "7") (pinfunction "RD+_7") (pintype "input"))
    )
    (net (code "134") (name "Net-(IC15-IO4)") (class "Default")
      (node (ref "IC15") (pin "5") (pinfunction "IO4_5") (pintype "bidirectional"))
      (node (ref "IC16") (pin "13") (pinfunction "RD-_13") (pintype "bidirectional"))
      (node (ref "R49") (pin "1") (pinfunction "1_1") (pintype "passive"))
      (node (ref "X5") (pin "8") (pinfunction "RD-_8") (pintype "input"))
    )
    (net (code "135") (name "Net-(IC16-CRS{slash}CRS_DV{slash}LED_CFG)") (class "Default")
      (node (ref "IC16") (pin "40") (pinfunction "CRS/CRS_DV/LED_CFG_40") (pintype "output"))
      (node (ref "RN1") (pin "5") (pinfunction "2_5") (pintype "passive"))
    )
    (net (code "136") (name "Net-(IC16-MDIX_EN(RX_ER))") (class "Default")
      (node (ref "IC16") (pin "41") (pinfunction "MDIX_EN(RX_ER)_41") (pintype "output"))
      (node (ref "RN2") (pin "8") (pinfunction "2_8") (pintype "passive"))
    )
    (net (code "137") (name "Net-(IC16-MII_MODE(RX_DV))") (class "Default")
      (node (ref "IC16") (pin "39") (pinfunction "MII_MODE(RX_DV)_39") (pintype "output"))
      (node (ref "JP11") (pin "2") (pinfunction "2_2") (pintype "passive"))
      (node (ref "RN1") (pin "6") (pinfunction "2_6") (pintype "passive"))
    )
    (net (code "138") (name "Net-(IC16-PFBIN1)") (class "Default")
      (node (ref "C65") (pin "1") (pinfunction "1_1") (pintype "passive"))
      (node (ref "C66") (pin "1") (pinfunction "1_1") (pintype "passive"))
      (node (ref "C67") (pin "+") (pinfunction "+_+") (pintype "passive"))
      (node (ref "C68") (pin "1") (pinfunction "1_1") (pintype "passive"))
      (node (ref "IC16") (pin "18") (pinfunction "PFBIN1_18") (pintype "input"))
      (node (ref "IC16") (pin "23") (pinfunction "PFBOUT_23") (pintype "output"))
      (node (ref "IC16") (pin "37") (pinfunction "PFBIN2_37") (pintype "input"))
    )
    (net (code "139") (name "Net-(IC16-PHYAD0(COL))") (class "Default")
      (node (ref "IC16") (pin "42") (pinfunction "PHYAD0(COL)_42") (pintype "output"))
      (node (ref "RN2") (pin "7") (pinfunction "2_7") (pintype "passive"))
    )
    (net (code "140") (name "Net-(IC16-PHYAD1(RXD1_0))") (class "Default")
      (node (ref "IC16") (pin "43") (pinfunction "PHYAD1(RXD1_0)_43") (pintype "output"))
      (node (ref "RN2") (pin "6") (pinfunction "2_6") (pintype "passive"))
    )
    (net (code "141") (name "Net-(IC16-PHYAD2(RXD1_1))") (class "Default")
      (node (ref "IC16") (pin "44") (pinfunction "PHYAD2(RXD1_1)_44") (pintype "output"))
      (node (ref "RN2") (pin "5") (pinfunction "2_5") (pintype "passive"))
    )
    (net (code "142") (name "Net-(IC16-PHYAD3(RXD1_2))") (class "Default")
      (node (ref "IC16") (pin "45") (pinfunction "PHYAD3(RXD1_2)_45") (pintype "output"))
      (node (ref "RN3") (pin "8") (pinfunction "2_8") (pintype "passive"))
    )
    (net (code "143") (name "Net-(IC16-PHYAD4(RXD1_3))") (class "Default")
      (node (ref "IC16") (pin "46") (pinfunction "PHYAD4(RXD1_3)_46") (pintype "output"))
      (node (ref "RN3") (pin "7") (pinfunction "2_7") (pintype "passive"))
    )
    (net (code "144") (name "Net-(IC16-PWR_DOWN{slash}INT)") (class "Default")
      (node (ref "IC16") (pin "7") (pinfunction "PWR_DOWN/INT_7") (pintype "input"))
      (node (ref "JP13") (pin "2") (pinfunction "2_2") (pintype "passive"))
    )
    (net (code "145") (name "Net-(IC16-RBIAS)") (class "Default")
      (node (ref "IC16") (pin "24") (pinfunction "RBIAS_24") (pintype "input"))
      (node (ref "R55") (pin "2") (pinfunction "2_2") (pintype "passive"))
    )
    (net (code "146") (name "Net-(IC16-RESERVED-20)") (class "Default")
      (node (ref "IC16") (pin "20") (pinfunction "RESERVED-20_20") (pintype "bidirectional"))
      (node (ref "R54") (pin "2") (pinfunction "2_2") (pintype "passive"))
    )
    (net (code "147") (name "Net-(IC16-RESERVED-21)") (class "Default")
      (node (ref "IC16") (pin "21") (pinfunction "RESERVED-21_21") (pintype "bidirectional"))
      (node (ref "R53") (pin "2") (pinfunction "2_2") (pintype "passive"))
    )
    (net (code "148") (name "Net-(IC16-RX_CLK)") (class "Default")
      (node (ref "IC16") (pin "38") (pinfunction "RX_CLK_38") (pintype "output"))
      (node (ref "RN1") (pin "7") (pinfunction "2_7") (pintype "passive"))
    )
    (net (code "149") (name "Net-(IC16-TXD_0)") (class "Default")
      (node (ref "IC16") (pin "3") (pinfunction "TXD_0_3") (pintype "input"))
      (node (ref "RN4") (pin "8") (pinfunction "2_8") (pintype "passive"))
    )
    (net (code "150") (name "Net-(IC16-TXD_1)") (class "Default")
      (node (ref "IC16") (pin "4") (pinfunction "TXD_1_4") (pintype "input"))
      (node (ref "RN4") (pin "7") (pinfunction "2_7") (pintype "passive"))
    )
    (net (code "151") (name "Net-(IC16-TXD_2)") (class "Default")
      (node (ref "IC16") (pin "5") (pinfunction "TXD_2_5") (pintype "input"))
      (node (ref "RN4") (pin "6") (pinfunction "2_6") (pintype "passive"))
    )
    (net (code "152") (name "Net-(IC16-TXD_3{slash}SNI_MODE)") (class "Default")
      (node (ref "IC16") (pin "6") (pinfunction "TXD_3/SNI_MODE_6") (pintype "input"))
      (node (ref "RN4") (pin "5") (pinfunction "2_5") (pintype "passive"))
    )
    (net (code "153") (name "Net-(IC16-TX_CLK)") (class "Default")
      (node (ref "IC16") (pin "1") (pinfunction "TX_CLK_1") (pintype "output"))
      (node (ref "RN3") (pin "6") (pinfunction "2_6") (pintype "passive"))
    )
    (net (code "154") (name "Net-(IC16-TX_EN)") (class "Default")
      (node (ref "IC16") (pin "2") (pinfunction "TX_EN_2") (pintype "input"))
      (node (ref "RN3") (pin "5") (pinfunction "2_5") (pintype "passive"))
    )
    (net (code "155") (name "Net-(IC16-X1)") (class "Default")
      (node (ref "IC16") (pin "34") (pinfunction "X1_34") (pintype "input"))
      (node (ref "RN1") (pin "8") (pinfunction "2_8") (pintype "passive"))
    )
    (net (code "156") (name "Net-(JP9-Pad2)") (class "Default")
      (node (ref "JP9") (pin "2") (pinfunction "2_2") (pintype "passive"))
      (node (ref "R45") (pin "2") (pinfunction "2_2") (pintype "passive"))
    )
    (net (code "157") (name "Net-(JP10-Pad1)") (class "Default")
      (node (ref "JP10") (pin "1") (pinfunction "1_1") (pintype "passive"))
      (node (ref "JP12") (pin "1") (pinfunction "1_1") (pintype "passive"))
      (node (ref "RN2") (pin "1") (pinfunction "1_1") (pintype "passive"))
    )
    (net (code "158") (name "Net-(JP10-Pad2)") (class "Default")
      (node (ref "JP10") (pin "2") (pinfunction "2_2") (pintype "passive"))
      (node (ref "R42") (pin "2") (pinfunction "2_2") (pintype "passive"))
    )
    (net (code "159") (name "Net-(JP11-Pad1)") (class "Default")
      (node (ref "JP11") (pin "1") (pinfunction "1_1") (pintype "passive"))
      (node (ref "R47") (pin "2") (pinfunction "2_2") (pintype "passive"))
    )
    (net (code "160") (name "Net-(JP13-Pad1)") (class "Default")
      (node (ref "JP13") (pin "1") (pinfunction "1_1") (pintype "passive"))
      (node (ref "R56") (pin "2") (pinfunction "2_2") (pintype "passive"))
    )
    (net (code "161") (name "Net-(LCD1-B0)") (class "Default")
      (node (ref "JP6") (pin "COM") (pinfunction "COM_COM") (pintype "passive"))
      (node (ref "LCD1") (pin "13") (pinfunction "G0_13") (pintype "input"))
      (node (ref "LCD1") (pin "14") (pinfunction "G1_14") (pintype "input"))
      (node (ref "LCD1") (pin "21") (pinfunction "B0_21") (pintype "input"))
      (node (ref "LCD1") (pin "22") (pinfunction "B1_22") (pintype "input"))
      (node (ref "LCD1") (pin "5") (pinfunction "R0_5") (pintype "input"))
      (node (ref "LCD1") (pin "6") (pinfunction "R1_6") (pintype "input"))
    )
    (net (code "162") (name "Net-(LCD1-RESET)") (class "Default")
      (node (ref "JP7") (pin "COM") (pinfunction "COM_COM") (pintype "passive"))
      (node (ref "LCD1") (pin "36") (pinfunction "RESET_36") (pintype "input"))
    )
    (net (code "163") (name "Net-(Q1-PadB)") (class "Default")
      (node (ref "Q1") (pin "B") (pinfunction "B_B") (pintype "passive"))
      (node (ref "R28") (pin "2") (pinfunction "2_2") (pintype "passive"))
    )
    (net (code "164") (name "Net-(Q1-PadC)") (class "Default")
      (node (ref "Q1") (pin "C") (pinfunction "C_C") (pintype "passive"))
      (node (ref "R25") (pin "1") (pinfunction "1_1") (pintype "passive"))
    )
    (net (code "165") (name "Net-(R1-Pad2)") (class "Default")
      (node (ref "R1") (pin "2") (pinfunction "2_2") (pintype "passive"))
      (node (ref "R5") (pin "2") (pinfunction "2_2") (pintype "passive"))
      (node (ref "SW2") (pin "A") (pinfunction "A_A") (pintype "passive"))
    )
    (net (code "166") (name "Net-(R2-Pad1)") (class "Default")
      (node (ref "R2") (pin "1") (pinfunction "1_1") (pintype "passive"))
      (node (ref "X3") (pin "1") (pinfunction "1_1") (pintype "passive"))
    )
    (net (code "167") (name "Net-(R2-Pad2)") (class "Default")
      (node (ref "R2") (pin "2") (pinfunction "2_2") (pintype "passive"))
      (node (ref "R3") (pin "1") (pinfunction "1_1") (pintype "passive"))
    )
    (net (code "168") (name "Net-(R6-Pad2)") (class "Default")
      (node (ref "R6") (pin "2") (pinfunction "2_2") (pintype "passive"))
      (node (ref "R7") (pin "1") (pinfunction "1_1") (pintype "passive"))
    )
    (net (code "169") (name "Net-(R10-Pad2)") (class "Default")
      (node (ref "R10") (pin "2") (pinfunction "2_2") (pintype "passive"))
      (node (ref "R9") (pin "2") (pinfunction "2_2") (pintype "passive"))
      (node (ref "SW2") (pin "B") (pinfunction "B_B") (pintype "passive"))
    )
    (net (code "170") (name "Net-(R25-Pad2)") (class "Default")
      (node (ref "R25") (pin "2") (pinfunction "2_2") (pintype "passive"))
      (node (ref "VBUS") (pin "C") (pinfunction "C_C") (pintype "passive"))
    )
    (net (code "171") (name "Net-(R32-Pad1)") (class "Default")
      (node (ref "R32") (pin "1") (pinfunction "1_1") (pintype "passive"))
      (node (ref "R33") (pin "2") (pinfunction "2_2") (pintype "passive"))
    )
    (net (code "172") (name "Net-(R37-Pad1)") (class "Default")
      (node (ref "R37") (pin "1") (pinfunction "1_1") (pintype "passive"))
      (node (ref "R38") (pin "2") (pinfunction "2_2") (pintype "passive"))
    )
    (net (code "173") (name "Net-(R46-Pad2)") (class "Default")
      (node (ref "R46") (pin "2") (pinfunction "2_2") (pintype "passive"))
      (node (ref "SPEED") (pin "A") (pinfunction "A_A") (pintype "passive"))
    )
    (net (code "174") (name "Net-(X3B-1)") (class "Default")
      (node (ref "R6") (pin "1") (pinfunction "1_1") (pintype "passive"))
      (node (ref "X3") (pin "2") (pinfunction "1_2") (pintype "passive"))
    )
    (net (code "175") (name "Net-(X4A-S)") (class "Default")
      (node (ref "JP5") (pin "2") (pinfunction "2_2") (pintype "passive"))
      (node (ref "R18") (pin "2") (pinfunction "2_2") (pintype "passive"))
      (node (ref "X4") (pin "1") (pinfunction "S_1") (pintype "passive"))
    )
    (net (code "176") (name "Net-(X5-GREEN-C)") (class "Default")
      (node (ref "R52") (pin "1") (pinfunction "1_1") (pintype "passive"))
      (node (ref "X5") (pin "10") (pinfunction "GREEN-C_10") (pintype "passive"))
    )
    (net (code "177") (name "Net-(X5-YELLOW-C)") (class "Default")
      (node (ref "R51") (pin "1") (pinfunction "1_1") (pintype "passive"))
      (node (ref "X5") (pin "11") (pinfunction "YELLOW-C_11") (pintype "passive"))
    )
    (net (code "178") (name "OE_SYNC") (class "Default")
      (node (ref "IC4") (pin "94") (pinfunction "PD13_94") (pintype "bidirectional"))
      (node (ref "X1") (pin "10") (pinfunction "1_10") (pintype "passive"))
    )
    (net (code "179") (name "PE") (class "Default")
      (node (ref "C1") (pin "1") (pinfunction "1_1") (pintype "passive"))
      (node (ref "C51") (pin "1") (pinfunction "1_1") (pintype "passive"))
      (node (ref "J2") (pin "SH1") (pinfunction "SH1_SH1") (pintype "bidirectional"))
      (node (ref "J2") (pin "SH1.1") (pinfunction "SH1_SH1.1") (pintype "bidirectional"))
      (node (ref "J2") (pin "SH2") (pinfunction "SH2_SH2") (pintype "bidirectional"))
      (node (ref "J2") (pin "SH2.2") (pinfunction "SH2_SH2.2") (pintype "bidirectional"))
      (node (ref "JP1") (pin "2") (pinfunction "2_2") (pintype "passive"))
      (node (ref "X2") (pin "1") (pinfunction "1_1") (pintype "passive"))
      (node (ref "X2") (pin "2") (pinfunction "1_2") (pintype "passive"))
      (node (ref "X5") (pin "SH") (pinfunction "SH_SH") (pintype "passive"))
      (node (ref "X5") (pin "SH2") (pinfunction "SH_SH2") (pintype "passive"))
    )
    (net (code "180") (name "PWR_DIRECT") (class "Default")
      (node (ref "IC4") (pin "110") (pinfunction "PG2_110") (pintype "bidirectional"))
      (node (ref "X2") (pin "12") (pinfunction "1_12") (pintype "passive"))
    )
    (net (code "181") (name "PWR_SSTART") (class "Default")
      (node (ref "IC4") (pin "111") (pinfunction "PG3_111") (pintype "bidirectional"))
      (node (ref "X2") (pin "11") (pinfunction "1_11") (pintype "passive"))
    )
    (net (code "182") (name "RCC_OSC32_IN") (class "Default")
      (node (ref "C10") (pin "1") (pinfunction "1_1") (pintype "passive"))
      (node (ref "IC4") (pin "9") (pinfunction "PC14_9") (pintype "bidirectional"))
      (node (ref "Y2") (pin "1") (pinfunction "1_1") (pintype "passive"))
    )
    (net (code "183") (name "RCC_OSC32_OUT") (class "Default")
      (node (ref "C12") (pin "1") (pinfunction "1_1") (pintype "passive"))
      (node (ref "IC4") (pin "10") (pinfunction "PC15_10") (pintype "bidirectional"))
      (node (ref "Y2") (pin "4") (pinfunction "2_4") (pintype "passive"))
    )
    (net (code "184") (name "RCC_OSC_IN") (class "Default")
      (node (ref "C9") (pin "2") (pinfunction "2_2") (pintype "passive"))
      (node (ref "IC4") (pin "29") (pinfunction "PH0_29") (pintype "bidirectional"))
      (node (ref "Y1") (pin "2") (pinfunction "2_2") (pintype "passive"))
    )
    (net (code "185") (name "RCC_OSC_OUT") (class "Default")
      (node (ref "C11") (pin "2") (pinfunction "2_2") (pintype "passive"))
      (node (ref "IC4") (pin "30") (pinfunction "PH1_30") (pintype "bidirectional"))
      (node (ref "Y1") (pin "1") (pinfunction "1_1") (pintype "passive"))
    )
    (net (code "186") (name "SDMMC1_CK") (class "Default")
      (node (ref "IC4") (pin "141") (pinfunction "PC12_141") (pintype "bidirectional"))
      (node (ref "J1") (pin "5") (pinfunction "CLK_5") (pintype "passive"))
    )
    (net (code "187") (name "SDMMC1_CMD") (class "Default")
      (node (ref "IC4") (pin "144") (pinfunction "PD2_144") (pintype "bidirectional"))
      (node (ref "J1") (pin "3") (pinfunction "CMD_3") (pintype "passive"))
      (node (ref "R22") (pin "2") (pinfunction "2_2") (pintype "passive"))
    )
    (net (code "188") (name "SDMMC1_D0") (class "Default")
      (node (ref "IC4") (pin "121") (pinfunction "PC8_121") (pintype "bidirectional"))
      (node (ref "J1") (pin "7") (pinfunction "DAT0_7") (pintype "passive"))
      (node (ref "R21") (pin "2") (pinfunction "2_2") (pintype "passive"))
    )
    (net (code "189") (name "SD_DETECT") (class "Default")
      (node (ref "IC4") (pin "24") (pinfunction "PF6_24") (pintype "bidirectional"))
      (node (ref "J1") (pin "SW1") (pinfunction "SW1_SW1") (pintype "passive"))
    )
    (net (code "190") (name "SPI2_CLK") (class "Default")
      (node (ref "IC4") (pin "133") (pinfunction "PI1_133") (pintype "bidirectional"))
      (node (ref "X1") (pin "32") (pinfunction "1_32") (pintype "passive"))
    )
    (net (code "191") (name "SPI2_CSA") (class "Default")
      (node (ref "IC4") (pin "93") (pinfunction "PD12_93") (pintype "bidirectional"))
      (node (ref "X1") (pin "28") (pinfunction "1_28") (pintype "passive"))
    )
    (net (code "192") (name "SPI2_CSB") (class "Default")
      (node (ref "IC4") (pin "92") (pinfunction "PD11_92") (pintype "bidirectional"))
      (node (ref "X1") (pin "27") (pinfunction "1_27") (pintype "passive"))
    )
    (net (code "193") (name "SPI2_IRQ") (class "Default")
      (node (ref "IC4") (pin "123") (pinfunction "PA8_123") (pintype "bidirectional"))
      (node (ref "X1") (pin "25") (pinfunction "1_25") (pintype "passive"))
    )
    (net (code "194") (name "SPI2_MISO") (class "Default")
      (node (ref "IC4") (pin "87") (pinfunction "PB14_87") (pintype "bidirectional"))
      (node (ref "X1") (pin "31") (pinfunction "1_31") (pintype "passive"))
    )
    (net (code "195") (name "SPI2_MOSI") (class "Default")
      (node (ref "IC4") (pin "134") (pinfunction "PI3_134") (pintype "bidirectional"))
      (node (ref "X1") (pin "33") (pinfunction "1_33") (pintype "passive"))
    )
    (net (code "196") (name "SPI4_CLK") (class "Default")
      (node (ref "IC4") (pin "1") (pinfunction "PE2_1") (pintype "bidirectional"))
      (node (ref "X1") (pin "23") (pinfunction "1_23") (pintype "passive"))
    )
    (net (code "197") (name "SPI4_CSA") (class "Default")
      (node (ref "IC4") (pin "2") (pinfunction "PE3_2") (pintype "bidirectional"))
      (node (ref "X1") (pin "22") (pinfunction "1_22") (pintype "passive"))
    )
    (net (code "198") (name "SPI4_CSB") (class "Default")
      (node (ref "IC4") (pin "3") (pinfunction "PE4_3") (pintype "bidirectional"))
      (node (ref "X1") (pin "21") (pinfunction "1_21") (pintype "passive"))
    )
    (net (code "199") (name "SPI4_IRQ") (class "Default")
      (node (ref "IC4") (pin "168") (pinfunction "PB9_168") (pintype "bidirectional"))
      (node (ref "X1") (pin "19") (pinfunction "1_19") (pintype "passive"))
    )
    (net (code "200") (name "SPI4_MISO") (class "Default")
      (node (ref "IC4") (pin "4") (pinfunction "PE5_4") (pintype "bidirectional"))
      (node (ref "X1") (pin "24") (pinfunction "1_24") (pintype "passive"))
    )
    (net (code "201") (name "SPI4_MOSI") (class "Default")
      (node (ref "IC4") (pin "5") (pinfunction "PE6_5") (pintype "bidirectional"))
      (node (ref "X1") (pin "26") (pinfunction "1_26") (pintype "passive"))
    )
    (net (code "202") (name "SPI5_CLK") (class "Default")
      (node (ref "IC4") (pin "25") (pinfunction "PF7_25") (pintype "bidirectional"))
      (node (ref "X1") (pin "17") (pinfunction "1_17") (pintype "passive"))
    )
    (net (code "203") (name "SPI5_CSA") (class "Default")
      (node (ref "IC4") (pin "157") (pinfunction "PG14_157") (pintype "bidirectional"))
      (node (ref "X1") (pin "11") (pinfunction "1_11") (pintype "passive"))
    )
    (net (code "204") (name "SPI5_CSB") (class "Default")
      (node (ref "IC4") (pin "156") (pinfunction "PG13_156") (pintype "bidirectional"))
      (node (ref "X1") (pin "13") (pinfunction "1_13") (pintype "passive"))
    )
    (net (code "205") (name "SPI5_IRQ") (class "Default")
      (node (ref "IC4") (pin "138") (pinfunction "PA15_138") (pintype "bidirectional"))
      (node (ref "X1") (pin "9") (pinfunction "1_9") (pintype "passive"))
    )
    (net (code "206") (name "SPI5_MISO") (class "Default")
      (node (ref "IC4") (pin "26") (pinfunction "PF8_26") (pintype "bidirectional"))
      (node (ref "X1") (pin "18") (pinfunction "1_18") (pintype "passive"))
    )
    (net (code "207") (name "SPI5_MOSI") (class "Default")
      (node (ref "IC4") (pin "27") (pinfunction "PF9_27") (pintype "bidirectional"))
      (node (ref "X1") (pin "20") (pinfunction "1_20") (pintype "passive"))
    )
    (net (code "208") (name "SYS_JTCK-SWCLK") (class "Default")
      (node (ref "IC4") (pin "137") (pinfunction "PA14_137") (pintype "bidirectional"))
      (node (ref "R20") (pin "1") (pinfunction "1_1") (pintype "passive"))
    )
    (net (code "209") (name "SYS_JTDO-SWO") (class "Default")
      (node (ref "IC4") (pin "161") (pinfunction "PB3_161") (pintype "bidirectional"))
      (node (ref "IC6") (pin "5") (pinfunction "IO4_5") (pintype "bidirectional"))
      (node (ref "X4") (pin "6") (pinfunction "S_6") (pintype "passive"))
    )
    (net (code "210") (name "SYS_JTMS-SWDIO") (class "Default")
      (node (ref "IC4") (pin "128") (pinfunction "PA13_128") (pintype "bidirectional"))
      (node (ref "R19") (pin "1") (pinfunction "1_1") (pintype "passive"))
    )
    (net (code "211") (name "TCK") (class "Default")
      (node (ref "IC6") (pin "1") (pinfunction "IO1_1") (pintype "bidirectional"))
      (node (ref "R20") (pin "2") (pinfunction "2_2") (pintype "passive"))
      (node (ref "X4") (pin "2") (pinfunction "S_2") (pintype "passive"))
    )
    (net (code "212") (name "TFT_BRIGHTNESS") (class "Default")
      (node (ref "IC10") (pin "4") (pinfunction "CTRL_4") (pintype "input"))
      (node (ref "IC4") (pin "88") (pinfunction "PB15_88") (pintype "bidirectional"))
    )
    (net (code "213") (name "TMS") (class "Default")
      (node (ref "IC6") (pin "2") (pinfunction "IO2_2") (pintype "bidirectional"))
      (node (ref "R19") (pin "2") (pinfunction "2_2") (pintype "passive"))
      (node (ref "X4") (pin "4") (pinfunction "S_4") (pintype "passive"))
    )
    (net (code "214") (name "USB_D_N") (class "Default")
      (node (ref "IC11") (pin "1") (pinfunction "IO1_1") (pintype "bidirectional"))
      (node (ref "J2") (pin "2") (pinfunction "D-_2") (pintype "passive"))
      (node (ref "R29") (pin "1") (pinfunction "1_1") (pintype "passive"))
    )
    (net (code "215") (name "USB_D_P") (class "Default")
      (node (ref "IC11") (pin "2") (pinfunction "IO2_2") (pintype "bidirectional"))
      (node (ref "J2") (pin "3") (pinfunction "D+_3") (pintype "passive"))
      (node (ref "R30") (pin "1") (pinfunction "1_1") (pintype "passive"))
    )
    (net (code "216") (name "USB_OTG_FS_D_N") (class "Default")
      (node (ref "IC4") (pin "126") (pinfunction "PA11_126") (pintype "bidirectional"))
      (node (ref "R29") (pin "2") (pinfunction "2_2") (pintype "passive"))
    )
    (net (code "217") (name "USB_OTG_FS_D_P") (class "Default")
      (node (ref "IC4") (pin "127") (pinfunction "PA12_127") (pintype "bidirectional"))
      (node (ref "R30") (pin "2") (pinfunction "2_2") (pintype "passive"))
    )
    (net (code "218") (name "USB_OTG_FS_ID") (class "Default")
      (node (ref "IC11") (pin "4") (pinfunction "IO3_4") (pintype "bidirectional"))
      (node (ref "IC4") (pin "125") (pinfunction "PA10_125") (pintype "bidirectional"))
      (node (ref "J2") (pin "4") (pinfunction "ID_4") (pintype "passive"))
    )
    (net (code "219") (name "USB_OTG_FS_PSO") (class "Default")
      (node (ref "IC4") (pin "147") (pinfunction "PD5_147") (pintype "bidirectional"))
      (node (ref "IC9") (pin "4") (pinfunction "EN_4") (pintype "input"))
    )
    (net (code "220") (name "USB_OTG_FS_VBUS") (class "Default")
      (node (ref "C49") (pin "+") (pinfunction "+_+") (pintype "passive"))
      (node (ref "C52") (pin "2") (pinfunction "2_2") (pintype "passive"))
      (node (ref "IC11") (pin "6") (pinfunction "VCC_6") (pintype "passive"))
      (node (ref "IC4") (pin "124") (pinfunction "PA9_124") (pintype "bidirectional"))
      (node (ref "IC9") (pin "1") (pinfunction "OUT_1") (pintype "output"))
      (node (ref "J2") (pin "1") (pinfunction "VCC_1") (pintype "passive"))
      (node (ref "R28") (pin "1") (pinfunction "1_1") (pintype "passive"))
    )
    (net (code "221") (name "USER_SW") (class "Default")
      (node (ref "C4") (pin "2") (pinfunction "2_2") (pintype "passive"))
      (node (ref "IC4") (pin "152") (pinfunction "PG9_152") (pintype "bidirectional"))
      (node (ref "SW1") (pin "1") (pinfunction "1_1") (pintype "passive"))
    )
    (net (code "222") (name "VBAT") (class "Default")
      (node (ref "IC4") (pin "6") (pinfunction "VBAT_6") (pintype "power_in"))
      (node (ref "JP4") (pin "COM") (pinfunction "COM_COM") (pintype "passive"))
    )
    (net (code "223") (name "VCAP1") (class "Default")
      (node (ref "C37") (pin "1") (pinfunction "1_1") (pintype "passive"))
      (node (ref "IC4") (pin "81") (pinfunction "VCAP_1_81") (pintype "power_in"))
    )
    (net (code "224") (name "VCAP2") (class "Default")
      (node (ref "C36") (pin "1") (pinfunction "1_1") (pintype "passive"))
      (node (ref "IC4") (pin "129") (pinfunction "VCAP_2_129") (pintype "power_in"))
    )
    (net (code "225") (name "VDD") (class "Default")
      (node (ref "C16") (pin "1") (pinfunction "1_1") (pintype "passive"))
      (node (ref "C17") (pin "1") (pinfunction "1_1") (pintype "passive"))
      (node (ref "C18") (pin "1") (pinfunction "1_1") (pintype "passive"))
      (node (ref "C19") (pin "1") (pinfunction "1_1") (pintype "passive"))
      (node (ref "C20") (pin "1") (pinfunction "1_1") (pintype "passive"))
      (node (ref "C21") (pin "1") (pinfunction "1_1") (pintype "passive"))
      (node (ref "C22") (pin "+") (pinfunction "+_+") (pintype "passive"))
      (node (ref "C23") (pin "1") (pinfunction "1_1") (pintype "passive"))
      (node (ref "C24") (pin "1") (pinfunction "1_1") (pintype "passive"))
      (node (ref "C25") (pin "1") (pinfunction "1_1") (pintype "passive"))
      (node (ref "C26") (pin "1") (pinfunction "1_1") (pintype "passive"))
      (node (ref "C27") (pin "1") (pinfunction "1_1") (pintype "passive"))
      (node (ref "C28") (pin "1") (pinfunction "1_1") (pintype "passive"))
      (node (ref "C29") (pin "1") (pinfunction "1_1") (pintype "passive"))
      (node (ref "C30") (pin "1") (pinfunction "1_1") (pintype "passive"))
      (node (ref "C31") (pin "1") (pinfunction "1_1") (pintype "passive"))
      (node (ref "C32") (pin "1") (pinfunction "1_1") (pintype "passive"))
      (node (ref "C33") (pin "1") (pinfunction "1_1") (pintype "passive"))
      (node (ref "FB1") (pin "P$1") (pinfunction "1_P$1") (pintype "passive"))
      (node (ref "IC4") (pin "118") (pinfunction "VDDUSB_118") (pintype "power_in"))
      (node (ref "IC4") (pin "131") (pinfunction "VDD_10_131") (pintype "power_in"))
      (node (ref "IC4") (pin "136") (pinfunction "VDD_11_136") (pintype "power_in"))
      (node (ref "IC4") (pin "149") (pinfunction "VDDSDMMC_149") (pintype "power_in"))
      (node (ref "IC4") (pin "15") (pinfunction "VDD_2_15") (pintype "power_in"))
      (node (ref "IC4") (pin "159") (pinfunction "VDD_12_159") (pintype "power_in"))
      (node (ref "IC4") (pin "171") (pinfunction "PDR_ON_171") (pintype "passive"))
      (node (ref "IC4") (pin "172") (pinfunction "VDD_172") (pintype "power_in"))
      (node (ref "IC4") (pin "23") (pinfunction "VDD_3_23") (pintype "power_in"))
      (node (ref "IC4") (pin "36") (pinfunction "VDD_4_36") (pintype "power_in"))
      (node (ref "IC4") (pin "49") (pinfunction "VDD_5_49") (pintype "power_in"))
      (node (ref "IC4") (pin "62") (pinfunction "VDD_6_62") (pintype "power_in"))
      (node (ref "IC4") (pin "72") (pinfunction "VDD_7_72") (pintype "power_in"))
      (node (ref "IC4") (pin "82") (pinfunction "VDD_8_82") (pintype "power_in"))
      (node (ref "IC4") (pin "96") (pinfunction "VDD_9_96") (pintype "power_in"))
      (node (ref "IC4") (pin "99") (pinfunction "VDDDSI_99") (pintype "power_in"))
      (node (ref "JP2") (pin "1") (pinfunction "1_1") (pintype "passive"))
      (node (ref "JP4") (pin "NO") (pinfunction "NO_NO") (pintype "passive"))
      (node (ref "R11") (pin "1") (pinfunction "1_1") (pintype "passive"))
    )
    (net (code "226") (name "VDDA") (class "Default")
      (node (ref "C34") (pin "1") (pinfunction "1_1") (pintype "passive"))
      (node (ref "C35") (pin "1") (pinfunction "1_1") (pintype "passive"))
      (node (ref "FB1") (pin "P$2") (pinfunction "2_P$2") (pintype "passive"))
      (node (ref "IC4") (pin "39") (pinfunction "VDDA_39") (pintype "power_in"))
      (node (ref "R17") (pin "2") (pinfunction "2_2") (pintype "passive"))
    )
    (net (code "227") (name "VLED+") (class "Default")
      (node (ref "C48") (pin "1") (pinfunction "1_1") (pintype "passive"))
      (node (ref "D2") (pin "C") (pinfunction "C_C") (pintype "passive"))
      (node (ref "LCD1") (pin "2") (pinfunction "VLED+_2") (pintype "power_in"))
      (node (ref "ZD3") (pin "C") (pinfunction "C_C") (pintype "passive"))
    )
    (net (code "228") (name "VLED-") (class "Default")
      (node (ref "IC10") (pin "3") (pinfunction "FB_3") (pintype "input"))
      (node (ref "LCD1") (pin "1") (pinfunction "VLED-_1") (pintype "power_in"))
      (node (ref "R26") (pin "1") (pinfunction "1_1") (pintype "passive"))
      (node (ref "ZD3") (pin "A") (pinfunction "A_A") (pintype "passive"))
    )
    (net (code "229") (name "VREF+") (class "Default")
      (node (ref "IC4") (pin "38") (pinfunction "VREF+_38") (pintype "power_in"))
      (node (ref "R17") (pin "1") (pinfunction "1_1") (pintype "passive"))
    )
    (net (code "230") (name "XL") (class "Default")
      (node (ref "IC13") (pin "4") (pinfunction "IO3_4") (pintype "bidirectional"))
      (node (ref "IC14") (pin "4") (pinfunction "X-_4") (pintype "input"))
      (node (ref "LCD1") (pin "39") (pinfunction "XL_39") (pintype "passive"))
    )
    (net (code "231") (name "XR") (class "Default")
      (node (ref "IC13") (pin "1") (pinfunction "IO1_1") (pintype "bidirectional"))
      (node (ref "IC14") (pin "2") (pinfunction "X+_2") (pintype "input"))
      (node (ref "LCD1") (pin "37") (pinfunction "XR_37") (pintype "passive"))
    )
    (net (code "232") (name "YD") (class "Default")
      (node (ref "IC13") (pin "2") (pinfunction "IO2_2") (pintype "bidirectional"))
      (node (ref "IC14") (pin "5") (pinfunction "Y-_5") (pintype "input"))
      (node (ref "LCD1") (pin "38") (pinfunction "YD_38") (pintype "passive"))
    )
    (net (code "233") (name "YU") (class "Default")
      (node (ref "IC13") (pin "5") (pinfunction "IO4_5") (pintype "bidirectional"))
      (node (ref "IC14") (pin "3") (pinfunction "Y+_3") (pintype "input"))
      (node (ref "LCD1") (pin "40") (pinfunction "YU_40") (pintype "passive"))
    )
    (net (code "234") (name "unconnected-(IC4A-PC11-Pad140)") (class "Default")
      (node (ref "IC4") (pin "140") (pinfunction "PC11_140") (pintype "bidirectional"))
    )
    (net (code "235") (name "unconnected-(IC4C-DSI_CKN-Pad105)") (class "Default")
      (node (ref "IC4") (pin "105") (pinfunction "DSI_CKN_105") (pintype "bidirectional"))
    )
    (net (code "236") (name "unconnected-(IC4C-DSI_CKP-Pad104)") (class "Default")
      (node (ref "IC4") (pin "104") (pinfunction "DSI_CKP_104") (pintype "bidirectional"))
    )
    (net (code "237") (name "unconnected-(IC4C-DSI_D0N-Pad102)") (class "Default")
      (node (ref "IC4") (pin "102") (pinfunction "DSI_D0N_102") (pintype "bidirectional"))
    )
    (net (code "238") (name "unconnected-(IC4C-DSI_D0P-Pad101)") (class "Default")
      (node (ref "IC4") (pin "101") (pinfunction "DSI_D0P_101") (pintype "bidirectional"))
    )
    (net (code "239") (name "unconnected-(IC4C-DSI_D1N-Pad108)") (class "Default")
      (node (ref "IC4") (pin "108") (pinfunction "DSI_D1N_108") (pintype "bidirectional"))
    )
    (net (code "240") (name "unconnected-(IC4C-DSI_D1P-Pad107)") (class "Default")
      (node (ref "IC4") (pin "107") (pinfunction "DSI_D1P_107") (pintype "bidirectional"))
    )
    (net (code "241") (name "unconnected-(IC7-A12{slash}NC-36-Pad36)") (class "Default")
      (node (ref "IC7") (pin "36") (pinfunction "A12/NC-36_36") (pintype "passive"))
    )
    (net (code "242") (name "unconnected-(IC7-NC-40-Pad40)") (class "Default")
      (node (ref "IC7") (pin "40") (pinfunction "NC-40_40") (pintype "no_connect"))
    )
    (net (code "243") (name "unconnected-(IC11-IO4-Pad5)") (class "Default")
      (node (ref "IC11") (pin "5") (pinfunction "IO4_5") (pintype "bidirectional"))
    )
    (net (code "244") (name "unconnected-(IC14-AUX-Pad16)") (class "Default")
      (node (ref "IC14") (pin "16") (pinfunction "AUX_16") (pintype "input"))
    )
    (net (code "245") (name "unconnected-(IC16-CLK_OUT-Pad25)") (class "Default")
      (node (ref "IC16") (pin "25") (pinfunction "CLK_OUT_25") (pintype "output"))
    )
    (net (code "246") (name "unconnected-(IC16-TCK-Pad8)") (class "Default")
      (node (ref "IC16") (pin "8") (pinfunction "TCK_8") (pintype "input"))
    )
    (net (code "247") (name "unconnected-(IC16-TDI-Pad12)") (class "Default")
      (node (ref "IC16") (pin "12") (pinfunction "TDI_12") (pintype "input"))
    )
    (net (code "248") (name "unconnected-(IC16-TDO-Pad9)") (class "Default")
      (node (ref "IC16") (pin "9") (pinfunction "TDO_9") (pintype "output"))
    )
    (net (code "249") (name "unconnected-(IC16-TMS-Pad10)") (class "Default")
      (node (ref "IC16") (pin "10") (pinfunction "TMS_10") (pintype "input"))
    )
    (net (code "250") (name "unconnected-(IC16-X2-Pad33)") (class "Default")
      (node (ref "IC16") (pin "33") (pinfunction "X2_33") (pintype "output"))
    )
    (net (code "251") (name "unconnected-(IC16-~{TRST}-Pad11)") (class "Default")
      (node (ref "IC16") (pin "11") (pinfunction "~{TRST}_11") (pintype "input"))
    )
    (net (code "252") (name "unconnected-(J1-CD{slash}DAT3-Pad2)") (class "Default")
      (node (ref "J1") (pin "2") (pinfunction "CD/DAT3_2") (pintype "passive"))
    )
    (net (code "253") (name "unconnected-(J1-DAT1-Pad8)") (class "Default")
      (node (ref "J1") (pin "8") (pinfunction "DAT1_8") (pintype "passive"))
    )
    (net (code "254") (name "unconnected-(J1-DAT2-Pad1)") (class "Default")
      (node (ref "J1") (pin "1") (pinfunction "DAT2_1") (pintype "passive"))
    )
    (net (code "255") (name "unconnected-(LCD1-NC1-Pad35)") (class "Default")
      (node (ref "LCD1") (pin "35") (pinfunction "NC1_35") (pintype "no_connect"))
    )
    (net (code "256") (name "unconnected-(SW3-NO-Pad3)") (class "Default")
      (node (ref "SW3") (pin "3") (pinfunction "NO_3") (pintype "passive"))
    )
    (net (code "257") (name "unconnected-(X1AH-1-Pad4)") (class "Default")
      (node (ref "X1") (pin "4") (pinfunction "1_4") (pintype "passive"))
    )
    (net (code "258") (name "unconnected-(X1W-1-Pad3)") (class "Default")
      (node (ref "X1") (pin "3") (pinfunction "1_3") (pintype "passive"))
    )
    (net (code "259") (name "~{FAULT}") (class "Default")
      (node (ref "IC3") (pin "1") (pinfunction "~{FAULT}_1") (pintype "output"))
      (node (ref "IC4") (pin "58") (pinfunction "PB2_58") (pintype "bidirectional"))
      (node (ref "R14") (pin "2") (pinfunction "2_2") (pintype "passive"))
      (node (ref "X1") (pin "8") (pinfunction "1_8") (pintype "passive"))
      (node (ref "X2") (pin "15") (pinfunction "1_15") (pintype "passive"))
    )
    (net (code "260") (name "~{RESET}") (class "Default")
      (node (ref "IC16") (pin "29") (pinfunction "RESET_N_29") (pintype "input"))
      (node (ref "IC3") (pin "4") (pinfunction "ENA_4") (pintype "input"))
      (node (ref "IC4") (pin "31") (pinfunction "NRST_31") (pintype "bidirectional"))
      (node (ref "IC6") (pin "4") (pinfunction "IO3_4") (pintype "bidirectional"))
      (node (ref "JP7") (pin "NO") (pinfunction "NO_NO") (pintype "passive"))
      (node (ref "R11") (pin "2") (pinfunction "2_2") (pintype "passive"))
      (node (ref "X1") (pin "6") (pinfunction "1_6") (pintype "passive"))
      (node (ref "X4") (pin "5") (pinfunction "S_5") (pintype "passive"))
    )
    (net (code "261") (name "~{USB_OTG_FS_OC}") (class "Default")
      (node (ref "IC4") (pin "146") (pinfunction "PD4_146") (pintype "bidirectional"))
      (node (ref "IC9") (pin "3") (pinfunction "~{OC}_3") (pintype "passive"))
      (node (ref "R27") (pin "1") (pinfunction "1_1") (pintype "passive"))
    )
  )
)
